# WestLaunch.net
KiCad netlist of a schematic drawn in EAGLE
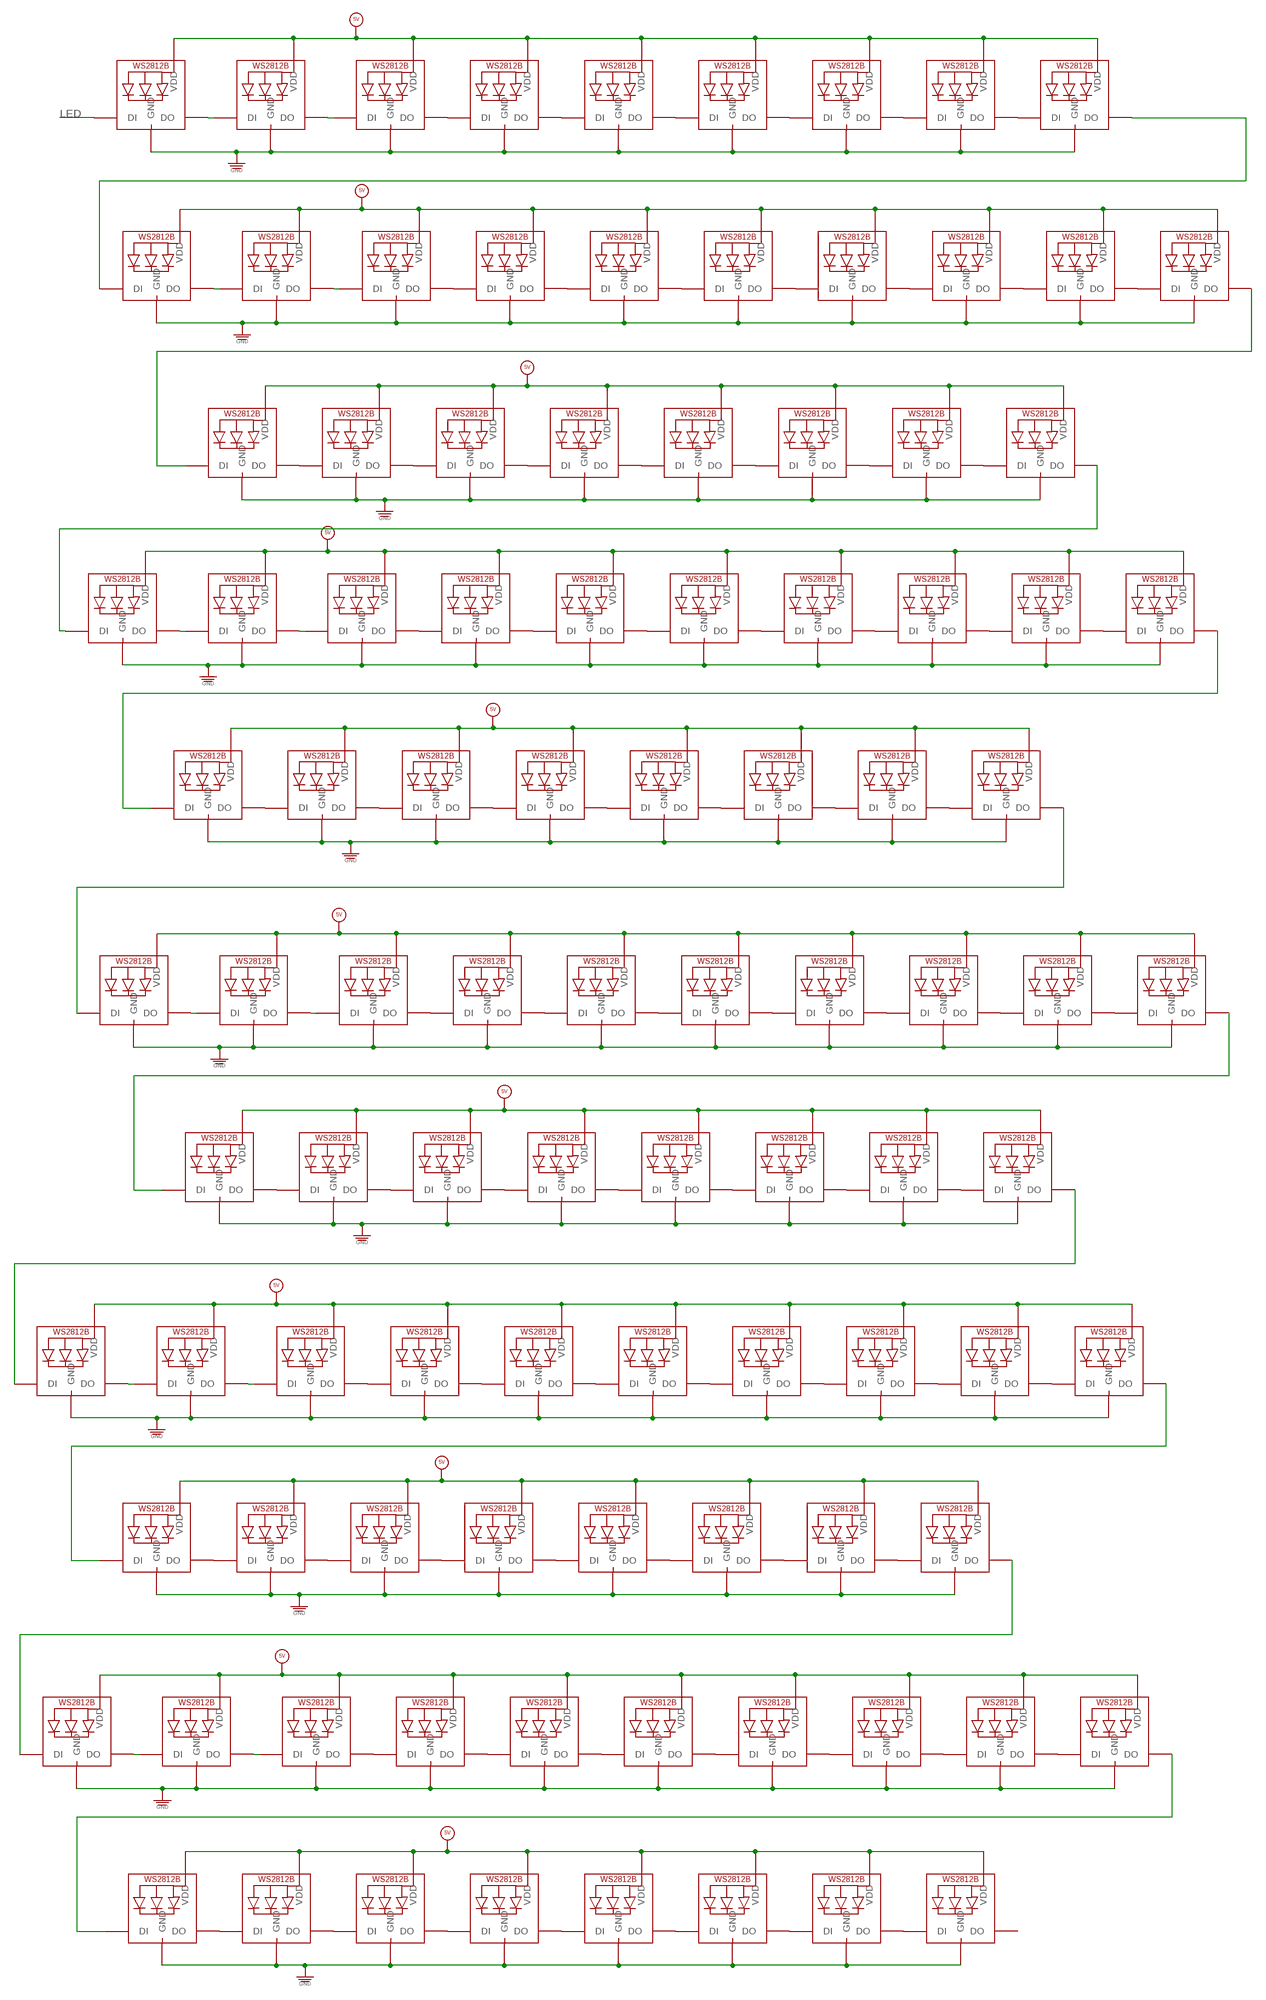
[diagram p0: schematic, sheet 1, part 1 of 2]
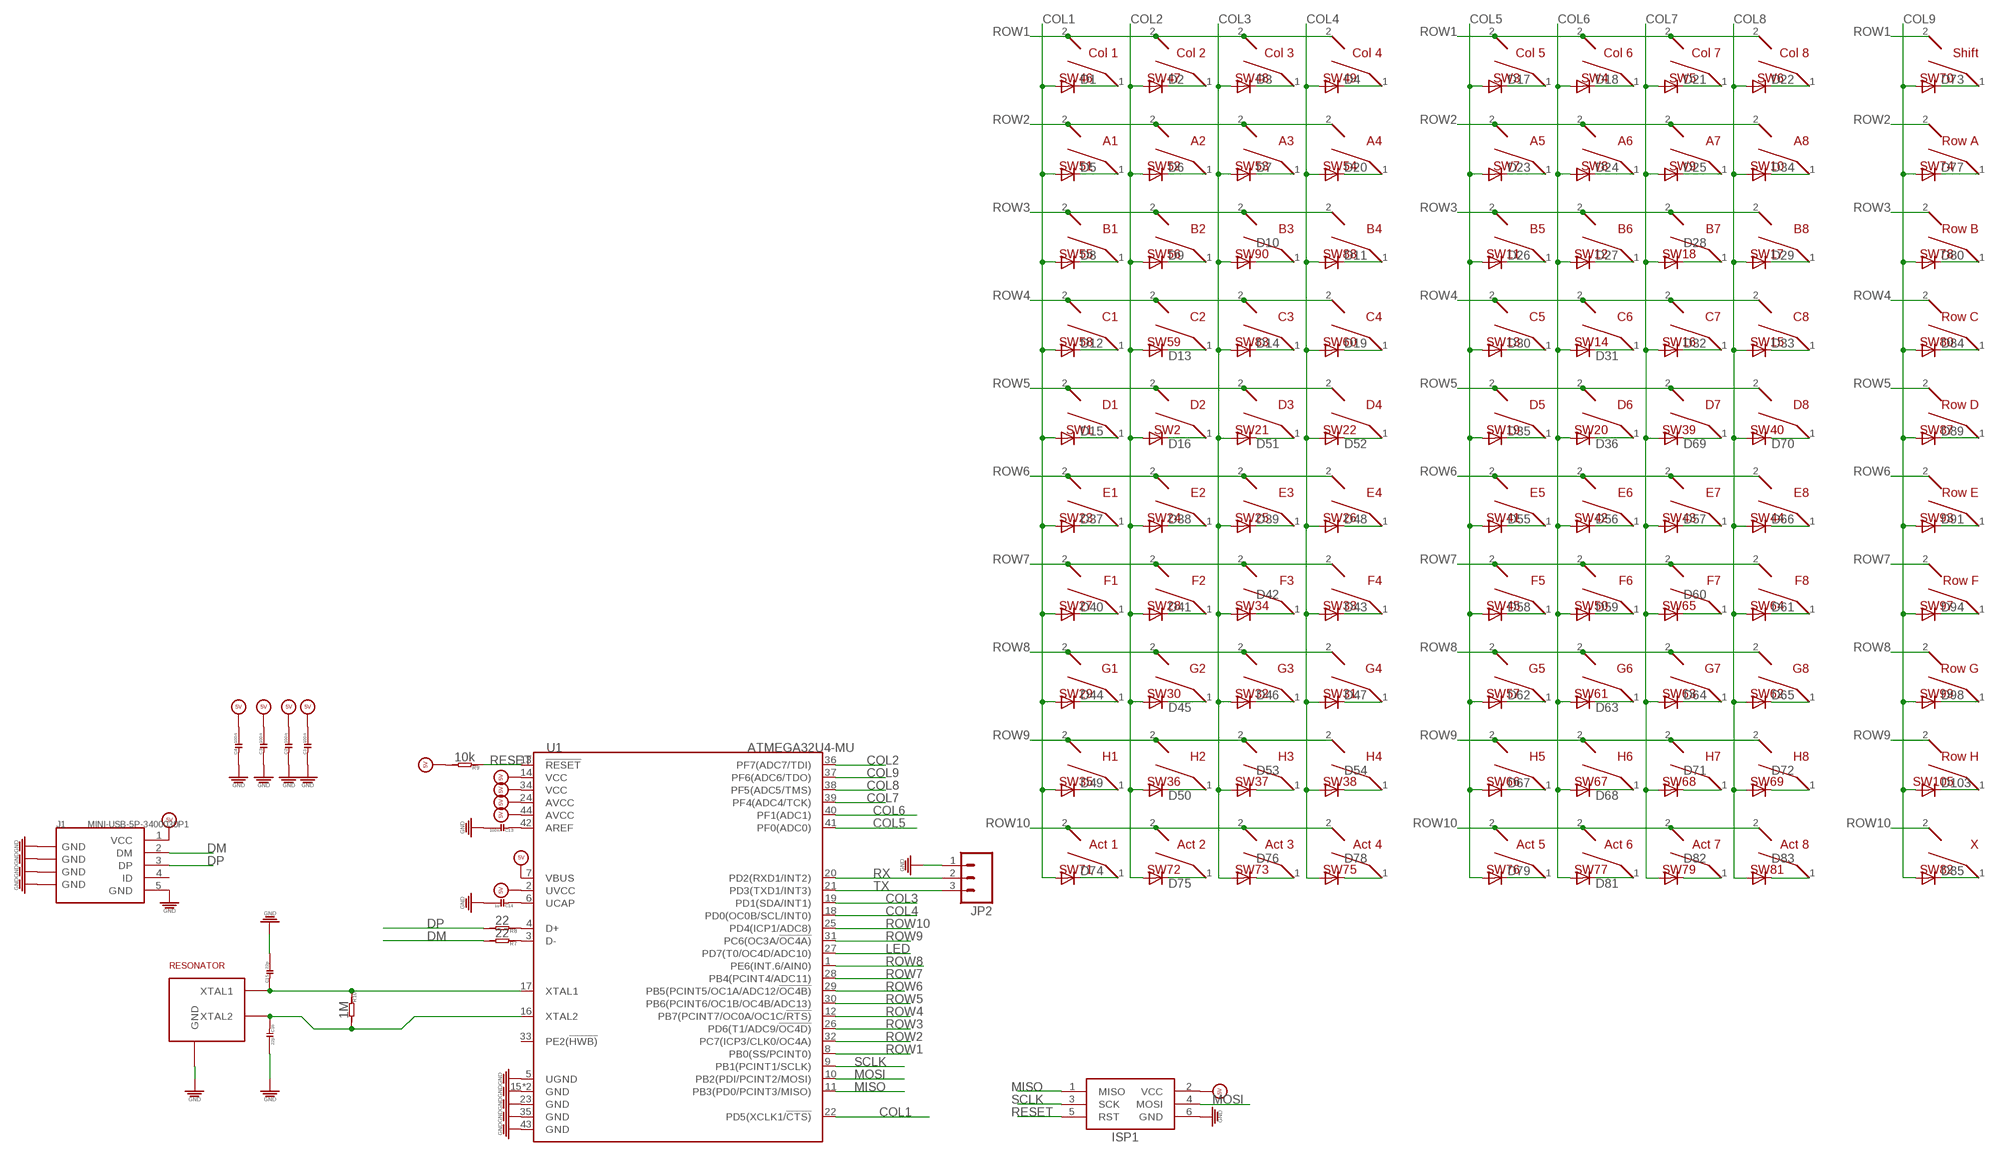
[diagram p1: schematic, sheet 1, part 2 of 2]

(export (version "E")
  (design (tool "Eeschema 10.0.6"))
  (components
    (comp (ref "C1")
      (value "100n")
      (footprint "eagle-import:C0603")
      (libsource (lib "eagle-import") (part "C-0603"))
    )
    (comp (ref "C2")
      (value "100n")
      (footprint "eagle-import:C0603")
      (libsource (lib "eagle-import") (part "C-0603"))
    )
    (comp (ref "C3")
      (value "100n")
      (footprint "eagle-import:C0603")
      (libsource (lib "eagle-import") (part "C-0603"))
    )
    (comp (ref "C4")
      (value "100n")
      (footprint "eagle-import:C0603")
      (libsource (lib "eagle-import") (part "C-0603"))
    )
    (comp (ref "C13")
      (value "100n")
      (footprint "eagle-import:C0603")
      (libsource (lib "eagle-import") (part "C-0603"))
    )
    (comp (ref "C14")
      (value "1u")
      (footprint "eagle-import:C0603")
      (libsource (lib "eagle-import") (part "C-0603"))
    )
    (comp (ref "C15")
      (value "22p")
      (footprint "eagle-import:C0603")
      (libsource (lib "eagle-import") (part "C-0603"))
    )
    (comp (ref "C16")
      (value "22p")
      (footprint "eagle-import:C0603")
      (libsource (lib "eagle-import") (part "C-0603"))
    )
    (comp (ref "D1")
      (value "CGRM4001-G")
      (footprint "eagle-import:SOD-123_MINI-SMA")
      (libsource (lib "eagle-import") (part "CGRM400-G1"))
    )
    (comp (ref "D2")
      (value "CGRM4001-G")
      (footprint "eagle-import:SOD-123_MINI-SMA")
      (libsource (lib "eagle-import") (part "CGRM400-G1"))
    )
    (comp (ref "D3")
      (value "CGRM4001-G")
      (footprint "eagle-import:SOD-123_MINI-SMA")
      (libsource (lib "eagle-import") (part "CGRM400-G1"))
    )
    (comp (ref "D4")
      (value "CGRM4001-G")
      (footprint "eagle-import:SOD-123_MINI-SMA")
      (libsource (lib "eagle-import") (part "CGRM400-G1"))
    )
    (comp (ref "D5")
      (value "CGRM4001-G")
      (footprint "eagle-import:SOD-123_MINI-SMA")
      (libsource (lib "eagle-import") (part "CGRM400-G1"))
    )
    (comp (ref "D6")
      (value "CGRM4001-G")
      (footprint "eagle-import:SOD-123_MINI-SMA")
      (libsource (lib "eagle-import") (part "CGRM400-G1"))
    )
    (comp (ref "D7")
      (value "CGRM4001-G")
      (footprint "eagle-import:SOD-123_MINI-SMA")
      (libsource (lib "eagle-import") (part "CGRM400-G1"))
    )
    (comp (ref "D8")
      (value "CGRM4001-G")
      (footprint "eagle-import:SOD-123_MINI-SMA")
      (libsource (lib "eagle-import") (part "CGRM400-G1"))
    )
    (comp (ref "D9")
      (value "CGRM4001-G")
      (footprint "eagle-import:SOD-123_MINI-SMA")
      (libsource (lib "eagle-import") (part "CGRM400-G1"))
    )
    (comp (ref "D10")
      (value "CGRM4001-G")
      (footprint "eagle-import:SOD-123_MINI-SMA")
      (libsource (lib "eagle-import") (part "CGRM400-G1"))
    )
    (comp (ref "D11")
      (value "CGRM4001-G")
      (footprint "eagle-import:SOD-123_MINI-SMA")
      (libsource (lib "eagle-import") (part "CGRM400-G1"))
    )
    (comp (ref "D12")
      (value "CGRM4001-G")
      (footprint "eagle-import:SOD-123_MINI-SMA")
      (libsource (lib "eagle-import") (part "CGRM400-G1"))
    )
    (comp (ref "D13")
      (value "CGRM4001-G")
      (footprint "eagle-import:SOD-123_MINI-SMA")
      (libsource (lib "eagle-import") (part "CGRM400-G1"))
    )
    (comp (ref "D14")
      (value "CGRM4001-G")
      (footprint "eagle-import:SOD-123_MINI-SMA")
      (libsource (lib "eagle-import") (part "CGRM400-G1"))
    )
    (comp (ref "D15")
      (value "CGRM4001-G")
      (footprint "eagle-import:SOD-123_MINI-SMA")
      (libsource (lib "eagle-import") (part "CGRM400-G1"))
    )
    (comp (ref "D16")
      (value "CGRM4001-G")
      (footprint "eagle-import:SOD-123_MINI-SMA")
      (libsource (lib "eagle-import") (part "CGRM400-G1"))
    )
    (comp (ref "D17")
      (value "CGRM4001-G")
      (footprint "eagle-import:SOD-123_MINI-SMA")
      (libsource (lib "eagle-import") (part "CGRM400-G1"))
    )
    (comp (ref "D18")
      (value "CGRM4001-G")
      (footprint "eagle-import:SOD-123_MINI-SMA")
      (libsource (lib "eagle-import") (part "CGRM400-G1"))
    )
    (comp (ref "D19")
      (value "CGRM4001-G")
      (footprint "eagle-import:SOD-123_MINI-SMA")
      (libsource (lib "eagle-import") (part "CGRM400-G1"))
    )
    (comp (ref "D20")
      (value "CGRM4001-G")
      (footprint "eagle-import:SOD-123_MINI-SMA")
      (libsource (lib "eagle-import") (part "CGRM400-G1"))
    )
    (comp (ref "D21")
      (value "CGRM4001-G")
      (footprint "eagle-import:SOD-123_MINI-SMA")
      (libsource (lib "eagle-import") (part "CGRM400-G1"))
    )
    (comp (ref "D22")
      (value "CGRM4001-G")
      (footprint "eagle-import:SOD-123_MINI-SMA")
      (libsource (lib "eagle-import") (part "CGRM400-G1"))
    )
    (comp (ref "D23")
      (value "CGRM4001-G")
      (footprint "eagle-import:SOD-123_MINI-SMA")
      (libsource (lib "eagle-import") (part "CGRM400-G1"))
    )
    (comp (ref "D24")
      (value "CGRM4001-G")
      (footprint "eagle-import:SOD-123_MINI-SMA")
      (libsource (lib "eagle-import") (part "CGRM400-G1"))
    )
    (comp (ref "D25")
      (value "CGRM4001-G")
      (footprint "eagle-import:SOD-123_MINI-SMA")
      (libsource (lib "eagle-import") (part "CGRM400-G1"))
    )
    (comp (ref "D26")
      (value "CGRM4001-G")
      (footprint "eagle-import:SOD-123_MINI-SMA")
      (libsource (lib "eagle-import") (part "CGRM400-G1"))
    )
    (comp (ref "D27")
      (value "CGRM4001-G")
      (footprint "eagle-import:SOD-123_MINI-SMA")
      (libsource (lib "eagle-import") (part "CGRM400-G1"))
    )
    (comp (ref "D28")
      (value "CGRM4001-G")
      (footprint "eagle-import:SOD-123_MINI-SMA")
      (libsource (lib "eagle-import") (part "CGRM400-G1"))
    )
    (comp (ref "D29")
      (value "CGRM4001-G")
      (footprint "eagle-import:SOD-123_MINI-SMA")
      (libsource (lib "eagle-import") (part "CGRM400-G1"))
    )
    (comp (ref "D30")
      (value "CGRM4001-G")
      (footprint "eagle-import:SOD-123_MINI-SMA")
      (libsource (lib "eagle-import") (part "CGRM400-G1"))
    )
    (comp (ref "D31")
      (value "CGRM4001-G")
      (footprint "eagle-import:SOD-123_MINI-SMA")
      (libsource (lib "eagle-import") (part "CGRM400-G1"))
    )
    (comp (ref "D32")
      (value "CGRM4001-G")
      (footprint "eagle-import:SOD-123_MINI-SMA")
      (libsource (lib "eagle-import") (part "CGRM400-G1"))
    )
    (comp (ref "D33")
      (value "CGRM4001-G")
      (footprint "eagle-import:SOD-123_MINI-SMA")
      (libsource (lib "eagle-import") (part "CGRM400-G1"))
    )
    (comp (ref "D34")
      (value "CGRM4001-G")
      (footprint "eagle-import:SOD-123_MINI-SMA")
      (libsource (lib "eagle-import") (part "CGRM400-G1"))
    )
    (comp (ref "D35")
      (value "CGRM4001-G")
      (footprint "eagle-import:SOD-123_MINI-SMA")
      (libsource (lib "eagle-import") (part "CGRM400-G1"))
    )
    (comp (ref "D36")
      (value "CGRM4001-G")
      (footprint "eagle-import:SOD-123_MINI-SMA")
      (libsource (lib "eagle-import") (part "CGRM400-G1"))
    )
    (comp (ref "D37")
      (value "CGRM4001-G")
      (footprint "eagle-import:SOD-123_MINI-SMA")
      (libsource (lib "eagle-import") (part "CGRM400-G1"))
    )
    (comp (ref "D38")
      (value "CGRM4001-G")
      (footprint "eagle-import:SOD-123_MINI-SMA")
      (libsource (lib "eagle-import") (part "CGRM400-G1"))
    )
    (comp (ref "D39")
      (value "CGRM4001-G")
      (footprint "eagle-import:SOD-123_MINI-SMA")
      (libsource (lib "eagle-import") (part "CGRM400-G1"))
    )
    (comp (ref "D40")
      (value "CGRM4001-G")
      (footprint "eagle-import:SOD-123_MINI-SMA")
      (libsource (lib "eagle-import") (part "CGRM400-G1"))
    )
    (comp (ref "D41")
      (value "CGRM4001-G")
      (footprint "eagle-import:SOD-123_MINI-SMA")
      (libsource (lib "eagle-import") (part "CGRM400-G1"))
    )
    (comp (ref "D42")
      (value "CGRM4001-G")
      (footprint "eagle-import:SOD-123_MINI-SMA")
      (libsource (lib "eagle-import") (part "CGRM400-G1"))
    )
    (comp (ref "D43")
      (value "CGRM4001-G")
      (footprint "eagle-import:SOD-123_MINI-SMA")
      (libsource (lib "eagle-import") (part "CGRM400-G1"))
    )
    (comp (ref "D44")
      (value "CGRM4001-G")
      (footprint "eagle-import:SOD-123_MINI-SMA")
      (libsource (lib "eagle-import") (part "CGRM400-G1"))
    )
    (comp (ref "D45")
      (value "CGRM4001-G")
      (footprint "eagle-import:SOD-123_MINI-SMA")
      (libsource (lib "eagle-import") (part "CGRM400-G1"))
    )
    (comp (ref "D46")
      (value "CGRM4001-G")
      (footprint "eagle-import:SOD-123_MINI-SMA")
      (libsource (lib "eagle-import") (part "CGRM400-G1"))
    )
    (comp (ref "D47")
      (value "CGRM4001-G")
      (footprint "eagle-import:SOD-123_MINI-SMA")
      (libsource (lib "eagle-import") (part "CGRM400-G1"))
    )
    (comp (ref "D48")
      (value "CGRM4001-G")
      (footprint "eagle-import:SOD-123_MINI-SMA")
      (libsource (lib "eagle-import") (part "CGRM400-G1"))
    )
    (comp (ref "D49")
      (value "CGRM4001-G")
      (footprint "eagle-import:SOD-123_MINI-SMA")
      (libsource (lib "eagle-import") (part "CGRM400-G1"))
    )
    (comp (ref "D50")
      (value "CGRM4001-G")
      (footprint "eagle-import:SOD-123_MINI-SMA")
      (libsource (lib "eagle-import") (part "CGRM400-G1"))
    )
    (comp (ref "D51")
      (value "CGRM4001-G")
      (footprint "eagle-import:SOD-123_MINI-SMA")
      (libsource (lib "eagle-import") (part "CGRM400-G1"))
    )
    (comp (ref "D52")
      (value "CGRM4001-G")
      (footprint "eagle-import:SOD-123_MINI-SMA")
      (libsource (lib "eagle-import") (part "CGRM400-G1"))
    )
    (comp (ref "D53")
      (value "CGRM4001-G")
      (footprint "eagle-import:SOD-123_MINI-SMA")
      (libsource (lib "eagle-import") (part "CGRM400-G1"))
    )
    (comp (ref "D54")
      (value "CGRM4001-G")
      (footprint "eagle-import:SOD-123_MINI-SMA")
      (libsource (lib "eagle-import") (part "CGRM400-G1"))
    )
    (comp (ref "D55")
      (value "CGRM4001-G")
      (footprint "eagle-import:SOD-123_MINI-SMA")
      (libsource (lib "eagle-import") (part "CGRM400-G1"))
    )
    (comp (ref "D56")
      (value "CGRM4001-G")
      (footprint "eagle-import:SOD-123_MINI-SMA")
      (libsource (lib "eagle-import") (part "CGRM400-G1"))
    )
    (comp (ref "D57")
      (value "CGRM4001-G")
      (footprint "eagle-import:SOD-123_MINI-SMA")
      (libsource (lib "eagle-import") (part "CGRM400-G1"))
    )
    (comp (ref "D58")
      (value "CGRM4001-G")
      (footprint "eagle-import:SOD-123_MINI-SMA")
      (libsource (lib "eagle-import") (part "CGRM400-G1"))
    )
    (comp (ref "D59")
      (value "CGRM4001-G")
      (footprint "eagle-import:SOD-123_MINI-SMA")
      (libsource (lib "eagle-import") (part "CGRM400-G1"))
    )
    (comp (ref "D60")
      (value "CGRM4001-G")
      (footprint "eagle-import:SOD-123_MINI-SMA")
      (libsource (lib "eagle-import") (part "CGRM400-G1"))
    )
    (comp (ref "D61")
      (value "CGRM4001-G")
      (footprint "eagle-import:SOD-123_MINI-SMA")
      (libsource (lib "eagle-import") (part "CGRM400-G1"))
    )
    (comp (ref "D62")
      (value "CGRM4001-G")
      (footprint "eagle-import:SOD-123_MINI-SMA")
      (libsource (lib "eagle-import") (part "CGRM400-G1"))
    )
    (comp (ref "D63")
      (value "CGRM4001-G")
      (footprint "eagle-import:SOD-123_MINI-SMA")
      (libsource (lib "eagle-import") (part "CGRM400-G1"))
    )
    (comp (ref "D64")
      (value "CGRM4001-G")
      (footprint "eagle-import:SOD-123_MINI-SMA")
      (libsource (lib "eagle-import") (part "CGRM400-G1"))
    )
    (comp (ref "D65")
      (value "CGRM4001-G")
      (footprint "eagle-import:SOD-123_MINI-SMA")
      (libsource (lib "eagle-import") (part "CGRM400-G1"))
    )
    (comp (ref "D66")
      (value "CGRM4001-G")
      (footprint "eagle-import:SOD-123_MINI-SMA")
      (libsource (lib "eagle-import") (part "CGRM400-G1"))
    )
    (comp (ref "D67")
      (value "CGRM4001-G")
      (footprint "eagle-import:SOD-123_MINI-SMA")
      (libsource (lib "eagle-import") (part "CGRM400-G1"))
    )
    (comp (ref "D68")
      (value "CGRM4001-G")
      (footprint "eagle-import:SOD-123_MINI-SMA")
      (libsource (lib "eagle-import") (part "CGRM400-G1"))
    )
    (comp (ref "D69")
      (value "CGRM4001-G")
      (footprint "eagle-import:SOD-123_MINI-SMA")
      (libsource (lib "eagle-import") (part "CGRM400-G1"))
    )
    (comp (ref "D70")
      (value "CGRM4001-G")
      (footprint "eagle-import:SOD-123_MINI-SMA")
      (libsource (lib "eagle-import") (part "CGRM400-G1"))
    )
    (comp (ref "D71")
      (value "CGRM4001-G")
      (footprint "eagle-import:SOD-123_MINI-SMA")
      (libsource (lib "eagle-import") (part "CGRM400-G1"))
    )
    (comp (ref "D72")
      (value "CGRM4001-G")
      (footprint "eagle-import:SOD-123_MINI-SMA")
      (libsource (lib "eagle-import") (part "CGRM400-G1"))
    )
    (comp (ref "D73")
      (value "CGRM4001-G")
      (footprint "eagle-import:SOD-123_MINI-SMA")
      (libsource (lib "eagle-import") (part "CGRM400-G1"))
    )
    (comp (ref "D74")
      (value "CGRM4001-G")
      (footprint "eagle-import:SOD-123_MINI-SMA")
      (libsource (lib "eagle-import") (part "CGRM400-G1"))
    )
    (comp (ref "D75")
      (value "CGRM4001-G")
      (footprint "eagle-import:SOD-123_MINI-SMA")
      (libsource (lib "eagle-import") (part "CGRM400-G1"))
    )
    (comp (ref "D76")
      (value "CGRM4001-G")
      (footprint "eagle-import:SOD-123_MINI-SMA")
      (libsource (lib "eagle-import") (part "CGRM400-G1"))
    )
    (comp (ref "D77")
      (value "CGRM4001-G")
      (footprint "eagle-import:SOD-123_MINI-SMA")
      (libsource (lib "eagle-import") (part "CGRM400-G1"))
    )
    (comp (ref "D78")
      (value "CGRM4001-G")
      (footprint "eagle-import:SOD-123_MINI-SMA")
      (libsource (lib "eagle-import") (part "CGRM400-G1"))
    )
    (comp (ref "D79")
      (value "CGRM4001-G")
      (footprint "eagle-import:SOD-123_MINI-SMA")
      (libsource (lib "eagle-import") (part "CGRM400-G1"))
    )
    (comp (ref "D80")
      (value "CGRM4001-G")
      (footprint "eagle-import:SOD-123_MINI-SMA")
      (libsource (lib "eagle-import") (part "CGRM400-G1"))
    )
    (comp (ref "D81")
      (value "CGRM4001-G")
      (footprint "eagle-import:SOD-123_MINI-SMA")
      (libsource (lib "eagle-import") (part "CGRM400-G1"))
    )
    (comp (ref "D82")
      (value "CGRM4001-G")
      (footprint "eagle-import:SOD-123_MINI-SMA")
      (libsource (lib "eagle-import") (part "CGRM400-G1"))
    )
    (comp (ref "D83")
      (value "CGRM4001-G")
      (footprint "eagle-import:SOD-123_MINI-SMA")
      (libsource (lib "eagle-import") (part "CGRM400-G1"))
    )
    (comp (ref "D84")
      (value "CGRM4001-G")
      (footprint "eagle-import:SOD-123_MINI-SMA")
      (libsource (lib "eagle-import") (part "CGRM400-G1"))
    )
    (comp (ref "D85")
      (value "CGRM4001-G")
      (footprint "eagle-import:SOD-123_MINI-SMA")
      (libsource (lib "eagle-import") (part "CGRM400-G1"))
    )
    (comp (ref "D89")
      (value "CGRM4001-G")
      (footprint "eagle-import:SOD-123_MINI-SMA")
      (libsource (lib "eagle-import") (part "CGRM400-G1"))
    )
    (comp (ref "D91")
      (value "CGRM4001-G")
      (footprint "eagle-import:SOD-123_MINI-SMA")
      (libsource (lib "eagle-import") (part "CGRM400-G1"))
    )
    (comp (ref "D94")
      (value "CGRM4001-G")
      (footprint "eagle-import:SOD-123_MINI-SMA")
      (libsource (lib "eagle-import") (part "CGRM400-G1"))
    )
    (comp (ref "D98")
      (value "CGRM4001-G")
      (footprint "eagle-import:SOD-123_MINI-SMA")
      (libsource (lib "eagle-import") (part "CGRM400-G1"))
    )
    (comp (ref "D103")
      (value "CGRM4001-G")
      (footprint "eagle-import:SOD-123_MINI-SMA")
      (libsource (lib "eagle-import") (part "CGRM400-G1"))
    )
    (comp (ref "ISP1")
      (value "AVRISP-6")
      (footprint "eagle-import:AVRISP")
      (libsource (lib "eagle-import") (part "AVRISP-6"))
    )
    (comp (ref "J1")
      (value "MINI-USB-5P-3400030P1")
      (footprint "eagle-import:MINI-B-5P-SMD")
      (libsource (lib "eagle-import") (part "MINI-USB-5P-3400030P1"))
    )
    (comp (ref "JP2")
      (value "M03PTH")
      (footprint "eagle-import:1X03")
      (fields (field (name "DESC") "Serial"))
      (libsource (lib "eagle-import") (part "M03PTH"))
    )
    (comp (ref "LED1")
      (value "WS2812B3535")
      (footprint "eagle-import:LED3535")
      (libsource (lib "eagle-import") (part "WS2812B3535"))
    )
    (comp (ref "LED2")
      (value "WS2812B3535")
      (footprint "eagle-import:LED3535")
      (libsource (lib "eagle-import") (part "WS2812B3535"))
    )
    (comp (ref "LED3")
      (value "WS2812B3535")
      (footprint "eagle-import:LED3535")
      (libsource (lib "eagle-import") (part "WS2812B3535"))
    )
    (comp (ref "LED4")
      (value "WS2812B3535")
      (footprint "eagle-import:LED3535")
      (libsource (lib "eagle-import") (part "WS2812B3535"))
    )
    (comp (ref "LED5")
      (value "WS2812B3535")
      (footprint "eagle-import:LED3535")
      (libsource (lib "eagle-import") (part "WS2812B3535"))
    )
    (comp (ref "LED6")
      (value "WS2812B3535")
      (footprint "eagle-import:LED3535")
      (libsource (lib "eagle-import") (part "WS2812B3535"))
    )
    (comp (ref "LED7")
      (value "WS2812B3535")
      (footprint "eagle-import:LED3535")
      (libsource (lib "eagle-import") (part "WS2812B3535"))
    )
    (comp (ref "LED8")
      (value "WS2812B3535")
      (footprint "eagle-import:LED3535")
      (libsource (lib "eagle-import") (part "WS2812B3535"))
    )
    (comp (ref "LED9")
      (value "WS2812B3535")
      (footprint "eagle-import:LED3535")
      (libsource (lib "eagle-import") (part "WS2812B3535"))
    )
    (comp (ref "LED10")
      (value "WS2812B3535")
      (footprint "eagle-import:LED3535")
      (libsource (lib "eagle-import") (part "WS2812B3535"))
    )
    (comp (ref "LED11")
      (value "WS2812B3535")
      (footprint "eagle-import:LED3535")
      (libsource (lib "eagle-import") (part "WS2812B3535"))
    )
    (comp (ref "LED12")
      (value "WS2812B3535")
      (footprint "eagle-import:LED3535")
      (libsource (lib "eagle-import") (part "WS2812B3535"))
    )
    (comp (ref "LED13")
      (value "WS2812B3535")
      (footprint "eagle-import:LED3535")
      (libsource (lib "eagle-import") (part "WS2812B3535"))
    )
    (comp (ref "LED14")
      (value "WS2812B3535")
      (footprint "eagle-import:LED3535")
      (libsource (lib "eagle-import") (part "WS2812B3535"))
    )
    (comp (ref "LED15")
      (value "WS2812B3535")
      (footprint "eagle-import:LED3535")
      (libsource (lib "eagle-import") (part "WS2812B3535"))
    )
    (comp (ref "LED16")
      (value "WS2812B3535")
      (footprint "eagle-import:LED3535")
      (libsource (lib "eagle-import") (part "WS2812B3535"))
    )
    (comp (ref "LED17")
      (value "WS2812B3535")
      (footprint "eagle-import:LED3535")
      (libsource (lib "eagle-import") (part "WS2812B3535"))
    )
    (comp (ref "LED18")
      (value "WS2812B3535")
      (footprint "eagle-import:LED3535")
      (libsource (lib "eagle-import") (part "WS2812B3535"))
    )
    (comp (ref "LED19")
      (value "WS2812B3535")
      (footprint "eagle-import:LED3535")
      (libsource (lib "eagle-import") (part "WS2812B3535"))
    )
    (comp (ref "LED20")
      (value "WS2812B3535")
      (footprint "eagle-import:LED3535")
      (libsource (lib "eagle-import") (part "WS2812B3535"))
    )
    (comp (ref "LED21")
      (value "WS2812B3535")
      (footprint "eagle-import:LED3535")
      (libsource (lib "eagle-import") (part "WS2812B3535"))
    )
    (comp (ref "LED22")
      (value "WS2812B3535")
      (footprint "eagle-import:LED3535")
      (libsource (lib "eagle-import") (part "WS2812B3535"))
    )
    (comp (ref "LED23")
      (value "WS2812B3535")
      (footprint "eagle-import:LED3535")
      (libsource (lib "eagle-import") (part "WS2812B3535"))
    )
    (comp (ref "LED24")
      (value "WS2812B3535")
      (footprint "eagle-import:LED3535")
      (libsource (lib "eagle-import") (part "WS2812B3535"))
    )
    (comp (ref "LED25")
      (value "WS2812B3535")
      (footprint "eagle-import:LED3535")
      (libsource (lib "eagle-import") (part "WS2812B3535"))
    )
    (comp (ref "LED26")
      (value "WS2812B3535")
      (footprint "eagle-import:LED3535")
      (libsource (lib "eagle-import") (part "WS2812B3535"))
    )
    (comp (ref "LED27")
      (value "WS2812B3535")
      (footprint "eagle-import:LED3535")
      (libsource (lib "eagle-import") (part "WS2812B3535"))
    )
    (comp (ref "LED28")
      (value "WS2812B3535")
      (footprint "eagle-import:LED3535")
      (libsource (lib "eagle-import") (part "WS2812B3535"))
    )
    (comp (ref "LED29")
      (value "WS2812B3535")
      (footprint "eagle-import:LED3535")
      (libsource (lib "eagle-import") (part "WS2812B3535"))
    )
    (comp (ref "LED30")
      (value "WS2812B3535")
      (footprint "eagle-import:LED3535")
      (libsource (lib "eagle-import") (part "WS2812B3535"))
    )
    (comp (ref "LED31")
      (value "WS2812B3535")
      (footprint "eagle-import:LED3535")
      (libsource (lib "eagle-import") (part "WS2812B3535"))
    )
    (comp (ref "LED32")
      (value "WS2812B3535")
      (footprint "eagle-import:LED3535")
      (libsource (lib "eagle-import") (part "WS2812B3535"))
    )
    (comp (ref "LED33")
      (value "WS2812B3535")
      (footprint "eagle-import:LED3535")
      (libsource (lib "eagle-import") (part "WS2812B3535"))
    )
    (comp (ref "LED34")
      (value "WS2812B3535")
      (footprint "eagle-import:LED3535")
      (libsource (lib "eagle-import") (part "WS2812B3535"))
    )
    (comp (ref "LED35")
      (value "WS2812B3535")
      (footprint "eagle-import:LED3535")
      (libsource (lib "eagle-import") (part "WS2812B3535"))
    )
    (comp (ref "LED36")
      (value "WS2812B3535")
      (footprint "eagle-import:LED3535")
      (libsource (lib "eagle-import") (part "WS2812B3535"))
    )
    (comp (ref "LED37")
      (value "WS2812B3535")
      (footprint "eagle-import:LED3535")
      (libsource (lib "eagle-import") (part "WS2812B3535"))
    )
    (comp (ref "LED38")
      (value "WS2812B3535")
      (footprint "eagle-import:LED3535")
      (libsource (lib "eagle-import") (part "WS2812B3535"))
    )
    (comp (ref "LED39")
      (value "WS2812B3535")
      (footprint "eagle-import:LED3535")
      (libsource (lib "eagle-import") (part "WS2812B3535"))
    )
    (comp (ref "LED40")
      (value "WS2812B3535")
      (footprint "eagle-import:LED3535")
      (libsource (lib "eagle-import") (part "WS2812B3535"))
    )
    (comp (ref "LED41")
      (value "WS2812B3535")
      (footprint "eagle-import:LED3535")
      (libsource (lib "eagle-import") (part "WS2812B3535"))
    )
    (comp (ref "LED42")
      (value "WS2812B3535")
      (footprint "eagle-import:LED3535")
      (libsource (lib "eagle-import") (part "WS2812B3535"))
    )
    (comp (ref "LED43")
      (value "WS2812B3535")
      (footprint "eagle-import:LED3535")
      (libsource (lib "eagle-import") (part "WS2812B3535"))
    )
    (comp (ref "LED44")
      (value "WS2812B3535")
      (footprint "eagle-import:LED3535")
      (libsource (lib "eagle-import") (part "WS2812B3535"))
    )
    (comp (ref "LED45")
      (value "WS2812B3535")
      (footprint "eagle-import:LED3535")
      (libsource (lib "eagle-import") (part "WS2812B3535"))
    )
    (comp (ref "LED46")
      (value "WS2812B3535")
      (footprint "eagle-import:LED3535")
      (libsource (lib "eagle-import") (part "WS2812B3535"))
    )
    (comp (ref "LED47")
      (value "WS2812B3535")
      (footprint "eagle-import:LED3535")
      (libsource (lib "eagle-import") (part "WS2812B3535"))
    )
    (comp (ref "LED48")
      (value "WS2812B3535")
      (footprint "eagle-import:LED3535")
      (libsource (lib "eagle-import") (part "WS2812B3535"))
    )
    (comp (ref "LED49")
      (value "WS2812B3535")
      (footprint "eagle-import:LED3535")
      (libsource (lib "eagle-import") (part "WS2812B3535"))
    )
    (comp (ref "LED50")
      (value "WS2812B3535")
      (footprint "eagle-import:LED3535")
      (libsource (lib "eagle-import") (part "WS2812B3535"))
    )
    (comp (ref "LED51")
      (value "WS2812B3535")
      (footprint "eagle-import:LED3535")
      (libsource (lib "eagle-import") (part "WS2812B3535"))
    )
    (comp (ref "LED52")
      (value "WS2812B3535")
      (footprint "eagle-import:LED3535")
      (libsource (lib "eagle-import") (part "WS2812B3535"))
    )
    (comp (ref "LED53")
      (value "WS2812B3535")
      (footprint "eagle-import:LED3535")
      (libsource (lib "eagle-import") (part "WS2812B3535"))
    )
    (comp (ref "LED54")
      (value "WS2812B3535")
      (footprint "eagle-import:LED3535")
      (libsource (lib "eagle-import") (part "WS2812B3535"))
    )
    (comp (ref "LED55")
      (value "WS2812B3535")
      (footprint "eagle-import:LED3535")
      (libsource (lib "eagle-import") (part "WS2812B3535"))
    )
    (comp (ref "LED56")
      (value "WS2812B3535")
      (footprint "eagle-import:LED3535")
      (libsource (lib "eagle-import") (part "WS2812B3535"))
    )
    (comp (ref "LED57")
      (value "WS2812B3535")
      (footprint "eagle-import:LED3535")
      (libsource (lib "eagle-import") (part "WS2812B3535"))
    )
    (comp (ref "LED58")
      (value "WS2812B3535")
      (footprint "eagle-import:LED3535")
      (libsource (lib "eagle-import") (part "WS2812B3535"))
    )
    (comp (ref "LED59")
      (value "WS2812B3535")
      (footprint "eagle-import:LED3535")
      (libsource (lib "eagle-import") (part "WS2812B3535"))
    )
    (comp (ref "LED60")
      (value "WS2812B3535")
      (footprint "eagle-import:LED3535")
      (libsource (lib "eagle-import") (part "WS2812B3535"))
    )
    (comp (ref "LED61")
      (value "WS2812B3535")
      (footprint "eagle-import:LED3535")
      (libsource (lib "eagle-import") (part "WS2812B3535"))
    )
    (comp (ref "LED62")
      (value "WS2812B3535")
      (footprint "eagle-import:LED3535")
      (libsource (lib "eagle-import") (part "WS2812B3535"))
    )
    (comp (ref "LED63")
      (value "WS2812B3535")
      (footprint "eagle-import:LED3535")
      (libsource (lib "eagle-import") (part "WS2812B3535"))
    )
    (comp (ref "LED64")
      (value "WS2812B3535")
      (footprint "eagle-import:LED3535")
      (libsource (lib "eagle-import") (part "WS2812B3535"))
    )
    (comp (ref "LED65")
      (value "WS2812B3535")
      (footprint "eagle-import:LED3535")
      (libsource (lib "eagle-import") (part "WS2812B3535"))
    )
    (comp (ref "LED66")
      (value "WS2812B3535")
      (footprint "eagle-import:LED3535")
      (libsource (lib "eagle-import") (part "WS2812B3535"))
    )
    (comp (ref "LED67")
      (value "WS2812B3535")
      (footprint "eagle-import:LED3535")
      (libsource (lib "eagle-import") (part "WS2812B3535"))
    )
    (comp (ref "LED68")
      (value "WS2812B3535")
      (footprint "eagle-import:LED3535")
      (libsource (lib "eagle-import") (part "WS2812B3535"))
    )
    (comp (ref "LED69")
      (value "WS2812B3535")
      (footprint "eagle-import:LED3535")
      (libsource (lib "eagle-import") (part "WS2812B3535"))
    )
    (comp (ref "LED70")
      (value "WS2812B3535")
      (footprint "eagle-import:LED3535")
      (libsource (lib "eagle-import") (part "WS2812B3535"))
    )
    (comp (ref "LED71")
      (value "WS2812B3535")
      (footprint "eagle-import:LED3535")
      (libsource (lib "eagle-import") (part "WS2812B3535"))
    )
    (comp (ref "LED72")
      (value "WS2812B3535")
      (footprint "eagle-import:LED3535")
      (libsource (lib "eagle-import") (part "WS2812B3535"))
    )
    (comp (ref "LED73")
      (value "WS2812B3535")
      (footprint "eagle-import:LED3535")
      (libsource (lib "eagle-import") (part "WS2812B3535"))
    )
    (comp (ref "LED74")
      (value "WS2812B3535")
      (footprint "eagle-import:LED3535")
      (libsource (lib "eagle-import") (part "WS2812B3535"))
    )
    (comp (ref "LED75")
      (value "WS2812B3535")
      (footprint "eagle-import:LED3535")
      (libsource (lib "eagle-import") (part "WS2812B3535"))
    )
    (comp (ref "LED76")
      (value "WS2812B3535")
      (footprint "eagle-import:LED3535")
      (libsource (lib "eagle-import") (part "WS2812B3535"))
    )
    (comp (ref "LED77")
      (value "WS2812B3535")
      (footprint "eagle-import:LED3535")
      (libsource (lib "eagle-import") (part "WS2812B3535"))
    )
    (comp (ref "LED78")
      (value "WS2812B3535")
      (footprint "eagle-import:LED3535")
      (libsource (lib "eagle-import") (part "WS2812B3535"))
    )
    (comp (ref "LED79")
      (value "WS2812B3535")
      (footprint "eagle-import:LED3535")
      (libsource (lib "eagle-import") (part "WS2812B3535"))
    )
    (comp (ref "LED80")
      (value "WS2812B3535")
      (footprint "eagle-import:LED3535")
      (libsource (lib "eagle-import") (part "WS2812B3535"))
    )
    (comp (ref "LED81")
      (value "WS2812B3535")
      (footprint "eagle-import:LED3535")
      (libsource (lib "eagle-import") (part "WS2812B3535"))
    )
    (comp (ref "LED82")
      (value "WS2812B3535")
      (footprint "eagle-import:LED3535")
      (libsource (lib "eagle-import") (part "WS2812B3535"))
    )
    (comp (ref "LED83")
      (value "WS2812B3535")
      (footprint "eagle-import:LED3535")
      (libsource (lib "eagle-import") (part "WS2812B3535"))
    )
    (comp (ref "LED84")
      (value "WS2812B3535")
      (footprint "eagle-import:LED3535")
      (libsource (lib "eagle-import") (part "WS2812B3535"))
    )
    (comp (ref "LED85")
      (value "WS2812B3535")
      (footprint "eagle-import:LED3535")
      (libsource (lib "eagle-import") (part "WS2812B3535"))
    )
    (comp (ref "LED86")
      (value "WS2812B3535")
      (footprint "eagle-import:LED3535")
      (libsource (lib "eagle-import") (part "WS2812B3535"))
    )
    (comp (ref "LED87")
      (value "WS2812B3535")
      (footprint "eagle-import:LED3535")
      (libsource (lib "eagle-import") (part "WS2812B3535"))
    )
    (comp (ref "LED88")
      (value "WS2812B3535")
      (footprint "eagle-import:LED3535")
      (libsource (lib "eagle-import") (part "WS2812B3535"))
    )
    (comp (ref "LED89")
      (value "WS2812B3535")
      (footprint "eagle-import:LED3535")
      (libsource (lib "eagle-import") (part "WS2812B3535"))
    )
    (comp (ref "LED90")
      (value "WS2812B3535")
      (footprint "eagle-import:LED3535")
      (libsource (lib "eagle-import") (part "WS2812B3535"))
    )
    (comp (ref "LED91")
      (value "WS2812B3535")
      (footprint "eagle-import:LED3535")
      (libsource (lib "eagle-import") (part "WS2812B3535"))
    )
    (comp (ref "LED92")
      (value "WS2812B3535")
      (footprint "eagle-import:LED3535")
      (libsource (lib "eagle-import") (part "WS2812B3535"))
    )
    (comp (ref "LED93")
      (value "WS2812B3535")
      (footprint "eagle-import:LED3535")
      (libsource (lib "eagle-import") (part "WS2812B3535"))
    )
    (comp (ref "LED94")
      (value "WS2812B3535")
      (footprint "eagle-import:LED3535")
      (libsource (lib "eagle-import") (part "WS2812B3535"))
    )
    (comp (ref "LED95")
      (value "WS2812B3535")
      (footprint "eagle-import:LED3535")
      (libsource (lib "eagle-import") (part "WS2812B3535"))
    )
    (comp (ref "LED96")
      (value "WS2812B3535")
      (footprint "eagle-import:LED3535")
      (libsource (lib "eagle-import") (part "WS2812B3535"))
    )
    (comp (ref "LED97")
      (value "WS2812B3535")
      (footprint "eagle-import:LED3535")
      (libsource (lib "eagle-import") (part "WS2812B3535"))
    )
    (comp (ref "LED98")
      (value "WS2812B3535")
      (footprint "eagle-import:LED3535")
      (libsource (lib "eagle-import") (part "WS2812B3535"))
    )
    (comp (ref "LED99")
      (value "WS2812B3535")
      (footprint "eagle-import:LED3535")
      (libsource (lib "eagle-import") (part "WS2812B3535"))
    )
    (comp (ref "R7")
      (value "22")
      (footprint "eagle-import:R0603")
      (libsource (lib "eagle-import") (part "R-0603"))
    )
    (comp (ref "R8")
      (value "22")
      (footprint "eagle-import:R0603")
      (libsource (lib "eagle-import") (part "R-0603"))
    )
    (comp (ref "R9")
      (value "10k")
      (footprint "eagle-import:R0603")
      (libsource (lib "eagle-import") (part "R-0603"))
    )
    (comp (ref "R10")
      (value "1M")
      (footprint "eagle-import:R0603")
      (libsource (lib "eagle-import") (part "R-0603"))
    )
    (comp (ref "SW1")
      (value "D1")
      (footprint "eagle-import:MX1A-XXNW")
      (libsource (lib "eagle-import") (part "CHERRY_MX_WITH_FIXING_PINS"))
    )
    (comp (ref "SW2")
      (value "D2")
      (footprint "eagle-import:MX1A-XXNW")
      (libsource (lib "eagle-import") (part "CHERRY_MX_WITH_FIXING_PINS"))
    )
    (comp (ref "SW3")
      (value "Col 5")
      (footprint "eagle-import:MX1A-XXNW")
      (libsource (lib "eagle-import") (part "CHERRY_MX_WITH_FIXING_PINS"))
    )
    (comp (ref "SW4")
      (value "Col 6")
      (footprint "eagle-import:MX1A-XXNW")
      (libsource (lib "eagle-import") (part "CHERRY_MX_WITH_FIXING_PINS"))
    )
    (comp (ref "SW5")
      (value "Col 7")
      (footprint "eagle-import:MX1A-XXNW")
      (libsource (lib "eagle-import") (part "CHERRY_MX_WITH_FIXING_PINS"))
    )
    (comp (ref "SW6")
      (value "Col 8")
      (footprint "eagle-import:MX1A-XXNW")
      (libsource (lib "eagle-import") (part "CHERRY_MX_WITH_FIXING_PINS"))
    )
    (comp (ref "SW7")
      (value "A5")
      (footprint "eagle-import:MX1A-XXNW")
      (libsource (lib "eagle-import") (part "CHERRY_MX_WITH_FIXING_PINS"))
    )
    (comp (ref "SW8")
      (value "A6")
      (footprint "eagle-import:MX1A-XXNW")
      (libsource (lib "eagle-import") (part "CHERRY_MX_WITH_FIXING_PINS"))
    )
    (comp (ref "SW9")
      (value "A7")
      (footprint "eagle-import:MX1A-XXNW")
      (libsource (lib "eagle-import") (part "CHERRY_MX_WITH_FIXING_PINS"))
    )
    (comp (ref "SW10")
      (value "A8")
      (footprint "eagle-import:MX1A-XXNW")
      (libsource (lib "eagle-import") (part "CHERRY_MX_WITH_FIXING_PINS"))
    )
    (comp (ref "SW11")
      (value "B5")
      (footprint "eagle-import:MX1A-XXNW")
      (libsource (lib "eagle-import") (part "CHERRY_MX_WITH_FIXING_PINS"))
    )
    (comp (ref "SW12")
      (value "B6")
      (footprint "eagle-import:MX1A-XXNW")
      (libsource (lib "eagle-import") (part "CHERRY_MX_WITH_FIXING_PINS"))
    )
    (comp (ref "SW13")
      (value "C5")
      (footprint "eagle-import:MX1A-XXNW")
      (libsource (lib "eagle-import") (part "CHERRY_MX_WITH_FIXING_PINS"))
    )
    (comp (ref "SW14")
      (value "C6")
      (footprint "eagle-import:MX1A-XXNW")
      (libsource (lib "eagle-import") (part "CHERRY_MX_WITH_FIXING_PINS"))
    )
    (comp (ref "SW15")
      (value "C8")
      (footprint "eagle-import:MX1A-XXNW")
      (libsource (lib "eagle-import") (part "CHERRY_MX_WITH_FIXING_PINS"))
    )
    (comp (ref "SW16")
      (value "C7")
      (footprint "eagle-import:MX1A-XXNW")
      (libsource (lib "eagle-import") (part "CHERRY_MX_WITH_FIXING_PINS"))
    )
    (comp (ref "SW17")
      (value "B8")
      (footprint "eagle-import:MX1A-XXNW")
      (libsource (lib "eagle-import") (part "CHERRY_MX_WITH_FIXING_PINS"))
    )
    (comp (ref "SW18")
      (value "B7")
      (footprint "eagle-import:MX1A-XXNW")
      (libsource (lib "eagle-import") (part "CHERRY_MX_WITH_FIXING_PINS"))
    )
    (comp (ref "SW19")
      (value "D5")
      (footprint "eagle-import:MX1A-XXNW")
      (libsource (lib "eagle-import") (part "CHERRY_MX_WITH_FIXING_PINS"))
    )
    (comp (ref "SW20")
      (value "D6")
      (footprint "eagle-import:MX1A-XXNW")
      (libsource (lib "eagle-import") (part "CHERRY_MX_WITH_FIXING_PINS"))
    )
    (comp (ref "SW21")
      (value "D3")
      (footprint "eagle-import:MX1A-XXNW")
      (libsource (lib "eagle-import") (part "CHERRY_MX_WITH_FIXING_PINS"))
    )
    (comp (ref "SW22")
      (value "D4")
      (footprint "eagle-import:MX1A-XXNW")
      (libsource (lib "eagle-import") (part "CHERRY_MX_WITH_FIXING_PINS"))
    )
    (comp (ref "SW23")
      (value "E1")
      (footprint "eagle-import:MX1A-XXNW")
      (libsource (lib "eagle-import") (part "CHERRY_MX_WITH_FIXING_PINS"))
    )
    (comp (ref "SW24")
      (value "E2")
      (footprint "eagle-import:MX1A-XXNW")
      (libsource (lib "eagle-import") (part "CHERRY_MX_WITH_FIXING_PINS"))
    )
    (comp (ref "SW25")
      (value "E3")
      (footprint "eagle-import:MX1A-XXNW")
      (libsource (lib "eagle-import") (part "CHERRY_MX_WITH_FIXING_PINS"))
    )
    (comp (ref "SW26")
      (value "E4")
      (footprint "eagle-import:MX1A-XXNW")
      (libsource (lib "eagle-import") (part "CHERRY_MX_WITH_FIXING_PINS"))
    )
    (comp (ref "SW27")
      (value "F1")
      (footprint "eagle-import:MX1A-XXNW")
      (libsource (lib "eagle-import") (part "CHERRY_MX_WITH_FIXING_PINS"))
    )
    (comp (ref "SW28")
      (value "F2")
      (footprint "eagle-import:MX1A-XXNW")
      (libsource (lib "eagle-import") (part "CHERRY_MX_WITH_FIXING_PINS"))
    )
    (comp (ref "SW29")
      (value "G1")
      (footprint "eagle-import:MX1A-XXNW")
      (libsource (lib "eagle-import") (part "CHERRY_MX_WITH_FIXING_PINS"))
    )
    (comp (ref "SW30")
      (value "G2")
      (footprint "eagle-import:MX1A-XXNW")
      (libsource (lib "eagle-import") (part "CHERRY_MX_WITH_FIXING_PINS"))
    )
    (comp (ref "SW31")
      (value "G4")
      (footprint "eagle-import:MX1A-XXNW")
      (libsource (lib "eagle-import") (part "CHERRY_MX_WITH_FIXING_PINS"))
    )
    (comp (ref "SW32")
      (value "G3")
      (footprint "eagle-import:MX1A-XXNW")
      (libsource (lib "eagle-import") (part "CHERRY_MX_WITH_FIXING_PINS"))
    )
    (comp (ref "SW33")
      (value "F4")
      (footprint "eagle-import:MX1A-XXNW")
      (libsource (lib "eagle-import") (part "CHERRY_MX_WITH_FIXING_PINS"))
    )
    (comp (ref "SW34")
      (value "F3")
      (footprint "eagle-import:MX1A-XXNW")
      (libsource (lib "eagle-import") (part "CHERRY_MX_WITH_FIXING_PINS"))
    )
    (comp (ref "SW35")
      (value "H1")
      (footprint "eagle-import:MX1A-XXNW")
      (libsource (lib "eagle-import") (part "CHERRY_MX_WITH_FIXING_PINS"))
    )
    (comp (ref "SW36")
      (value "H2")
      (footprint "eagle-import:MX1A-XXNW")
      (libsource (lib "eagle-import") (part "CHERRY_MX_WITH_FIXING_PINS"))
    )
    (comp (ref "SW37")
      (value "H3")
      (footprint "eagle-import:MX1A-XXNW")
      (libsource (lib "eagle-import") (part "CHERRY_MX_WITH_FIXING_PINS"))
    )
    (comp (ref "SW38")
      (value "H4")
      (footprint "eagle-import:MX1A-XXNW")
      (libsource (lib "eagle-import") (part "CHERRY_MX_WITH_FIXING_PINS"))
    )
    (comp (ref "SW39")
      (value "D7")
      (footprint "eagle-import:MX1A-XXNW")
      (libsource (lib "eagle-import") (part "CHERRY_MX_WITH_FIXING_PINS"))
    )
    (comp (ref "SW40")
      (value "D8")
      (footprint "eagle-import:MX1A-XXNW")
      (libsource (lib "eagle-import") (part "CHERRY_MX_WITH_FIXING_PINS"))
    )
    (comp (ref "SW41")
      (value "E5")
      (footprint "eagle-import:MX1A-XXNW")
      (libsource (lib "eagle-import") (part "CHERRY_MX_WITH_FIXING_PINS"))
    )
    (comp (ref "SW42")
      (value "E6")
      (footprint "eagle-import:MX1A-XXNW")
      (libsource (lib "eagle-import") (part "CHERRY_MX_WITH_FIXING_PINS"))
    )
    (comp (ref "SW43")
      (value "E7")
      (footprint "eagle-import:MX1A-XXNW")
      (libsource (lib "eagle-import") (part "CHERRY_MX_WITH_FIXING_PINS"))
    )
    (comp (ref "SW44")
      (value "E8")
      (footprint "eagle-import:MX1A-XXNW")
      (libsource (lib "eagle-import") (part "CHERRY_MX_WITH_FIXING_PINS"))
    )
    (comp (ref "SW45")
      (value "F5")
      (footprint "eagle-import:MX1A-XXNW")
      (libsource (lib "eagle-import") (part "CHERRY_MX_WITH_FIXING_PINS"))
    )
    (comp (ref "SW46")
      (value "Col 1")
      (footprint "eagle-import:MX1A-XXNW")
      (libsource (lib "eagle-import") (part "CHERRY_MX_WITH_FIXING_PINS"))
    )
    (comp (ref "SW47")
      (value "Col 2")
      (footprint "eagle-import:MX1A-XXNW")
      (libsource (lib "eagle-import") (part "CHERRY_MX_WITH_FIXING_PINS"))
    )
    (comp (ref "SW48")
      (value "Col 3")
      (footprint "eagle-import:MX1A-XXNW")
      (libsource (lib "eagle-import") (part "CHERRY_MX_WITH_FIXING_PINS"))
    )
    (comp (ref "SW49")
      (value "Col 4")
      (footprint "eagle-import:MX1A-XXNW")
      (libsource (lib "eagle-import") (part "CHERRY_MX_WITH_FIXING_PINS"))
    )
    (comp (ref "SW50")
      (value "F6")
      (footprint "eagle-import:MX1A-XXNW")
      (libsource (lib "eagle-import") (part "CHERRY_MX_WITH_FIXING_PINS"))
    )
    (comp (ref "SW51")
      (value "A1")
      (footprint "eagle-import:MX1A-XXNW")
      (libsource (lib "eagle-import") (part "CHERRY_MX_WITH_FIXING_PINS"))
    )
    (comp (ref "SW52")
      (value "A2")
      (footprint "eagle-import:MX1A-XXNW")
      (libsource (lib "eagle-import") (part "CHERRY_MX_WITH_FIXING_PINS"))
    )
    (comp (ref "SW53")
      (value "A3")
      (footprint "eagle-import:MX1A-XXNW")
      (libsource (lib "eagle-import") (part "CHERRY_MX_WITH_FIXING_PINS"))
    )
    (comp (ref "SW54")
      (value "A4")
      (footprint "eagle-import:MX1A-XXNW")
      (libsource (lib "eagle-import") (part "CHERRY_MX_WITH_FIXING_PINS"))
    )
    (comp (ref "SW55")
      (value "B1")
      (footprint "eagle-import:MX1A-XXNW")
      (libsource (lib "eagle-import") (part "CHERRY_MX_WITH_FIXING_PINS"))
    )
    (comp (ref "SW56")
      (value "B2")
      (footprint "eagle-import:MX1A-XXNW")
      (libsource (lib "eagle-import") (part "CHERRY_MX_WITH_FIXING_PINS"))
    )
    (comp (ref "SW57")
      (value "G5")
      (footprint "eagle-import:MX1A-XXNW")
      (libsource (lib "eagle-import") (part "CHERRY_MX_WITH_FIXING_PINS"))
    )
    (comp (ref "SW58")
      (value "C1")
      (footprint "eagle-import:MX1A-XXNW")
      (libsource (lib "eagle-import") (part "CHERRY_MX_WITH_FIXING_PINS"))
    )
    (comp (ref "SW59")
      (value "C2")
      (footprint "eagle-import:MX1A-XXNW")
      (libsource (lib "eagle-import") (part "CHERRY_MX_WITH_FIXING_PINS"))
    )
    (comp (ref "SW60")
      (value "C4")
      (footprint "eagle-import:MX1A-XXNW")
      (libsource (lib "eagle-import") (part "CHERRY_MX_WITH_FIXING_PINS"))
    )
    (comp (ref "SW61")
      (value "G6")
      (footprint "eagle-import:MX1A-XXNW")
      (libsource (lib "eagle-import") (part "CHERRY_MX_WITH_FIXING_PINS"))
    )
    (comp (ref "SW62")
      (value "G8")
      (footprint "eagle-import:MX1A-XXNW")
      (libsource (lib "eagle-import") (part "CHERRY_MX_WITH_FIXING_PINS"))
    )
    (comp (ref "SW63")
      (value "G7")
      (footprint "eagle-import:MX1A-XXNW")
      (libsource (lib "eagle-import") (part "CHERRY_MX_WITH_FIXING_PINS"))
    )
    (comp (ref "SW64")
      (value "F8")
      (footprint "eagle-import:MX1A-XXNW")
      (libsource (lib "eagle-import") (part "CHERRY_MX_WITH_FIXING_PINS"))
    )
    (comp (ref "SW65")
      (value "F7")
      (footprint "eagle-import:MX1A-XXNW")
      (libsource (lib "eagle-import") (part "CHERRY_MX_WITH_FIXING_PINS"))
    )
    (comp (ref "SW66")
      (value "H5")
      (footprint "eagle-import:MX1A-XXNW")
      (libsource (lib "eagle-import") (part "CHERRY_MX_WITH_FIXING_PINS"))
    )
    (comp (ref "SW67")
      (value "H6")
      (footprint "eagle-import:MX1A-XXNW")
      (libsource (lib "eagle-import") (part "CHERRY_MX_WITH_FIXING_PINS"))
    )
    (comp (ref "SW68")
      (value "H7")
      (footprint "eagle-import:MX1A-XXNW")
      (libsource (lib "eagle-import") (part "CHERRY_MX_WITH_FIXING_PINS"))
    )
    (comp (ref "SW69")
      (value "H8")
      (footprint "eagle-import:MX1A-XXNW")
      (libsource (lib "eagle-import") (part "CHERRY_MX_WITH_FIXING_PINS"))
    )
    (comp (ref "SW70")
      (value "Shift")
      (footprint "eagle-import:MX1A-XXNW")
      (libsource (lib "eagle-import") (part "CHERRY_MX_WITH_FIXING_PINS"))
    )
    (comp (ref "SW71")
      (value "Act 1")
      (footprint "eagle-import:MX1A-XXNW")
      (libsource (lib "eagle-import") (part "CHERRY_MX_WITH_FIXING_PINS"))
    )
    (comp (ref "SW72")
      (value "Act 2")
      (footprint "eagle-import:MX1A-XXNW")
      (libsource (lib "eagle-import") (part "CHERRY_MX_WITH_FIXING_PINS"))
    )
    (comp (ref "SW73")
      (value "Act 3")
      (footprint "eagle-import:MX1A-XXNW")
      (libsource (lib "eagle-import") (part "CHERRY_MX_WITH_FIXING_PINS"))
    )
    (comp (ref "SW74")
      (value "Row A")
      (footprint "eagle-import:MX1A-XXNW")
      (libsource (lib "eagle-import") (part "CHERRY_MX_WITH_FIXING_PINS"))
    )
    (comp (ref "SW75")
      (value "Act 4")
      (footprint "eagle-import:MX1A-XXNW")
      (libsource (lib "eagle-import") (part "CHERRY_MX_WITH_FIXING_PINS"))
    )
    (comp (ref "SW76")
      (value "Act 5")
      (footprint "eagle-import:MX1A-XXNW")
      (libsource (lib "eagle-import") (part "CHERRY_MX_WITH_FIXING_PINS"))
    )
    (comp (ref "SW77")
      (value "Act 6")
      (footprint "eagle-import:MX1A-XXNW")
      (libsource (lib "eagle-import") (part "CHERRY_MX_WITH_FIXING_PINS"))
    )
    (comp (ref "SW78")
      (value "Row B")
      (footprint "eagle-import:MX1A-XXNW")
      (libsource (lib "eagle-import") (part "CHERRY_MX_WITH_FIXING_PINS"))
    )
    (comp (ref "SW79")
      (value "Act 7")
      (footprint "eagle-import:MX1A-XXNW")
      (libsource (lib "eagle-import") (part "CHERRY_MX_WITH_FIXING_PINS"))
    )
    (comp (ref "SW80")
      (value "Row C")
      (footprint "eagle-import:MX1A-XXNW")
      (libsource (lib "eagle-import") (part "CHERRY_MX_WITH_FIXING_PINS"))
    )
    (comp (ref "SW81")
      (value "Act 8")
      (footprint "eagle-import:MX1A-XXNW")
      (libsource (lib "eagle-import") (part "CHERRY_MX_WITH_FIXING_PINS"))
    )
    (comp (ref "SW82")
      (value "X")
      (footprint "eagle-import:MX1A-XXNW")
      (libsource (lib "eagle-import") (part "CHERRY_MX_WITH_FIXING_PINS"))
    )
    (comp (ref "SW83")
      (value "C3")
      (footprint "eagle-import:MX1A-XXNW")
      (libsource (lib "eagle-import") (part "CHERRY_MX_WITH_FIXING_PINS"))
    )
    (comp (ref "SW87")
      (value "Row D")
      (footprint "eagle-import:MX1A-XXNW")
      (libsource (lib "eagle-import") (part "CHERRY_MX_WITH_FIXING_PINS"))
    )
    (comp (ref "SW88")
      (value "B4")
      (footprint "eagle-import:MX1A-XXNW")
      (libsource (lib "eagle-import") (part "CHERRY_MX_WITH_FIXING_PINS"))
    )
    (comp (ref "SW90")
      (value "B3")
      (footprint "eagle-import:MX1A-XXNW")
      (libsource (lib "eagle-import") (part "CHERRY_MX_WITH_FIXING_PINS"))
    )
    (comp (ref "SW93")
      (value "Row E")
      (footprint "eagle-import:MX1A-XXNW")
      (libsource (lib "eagle-import") (part "CHERRY_MX_WITH_FIXING_PINS"))
    )
    (comp (ref "SW97")
      (value "Row F")
      (footprint "eagle-import:MX1A-XXNW")
      (libsource (lib "eagle-import") (part "CHERRY_MX_WITH_FIXING_PINS"))
    )
    (comp (ref "SW99")
      (value "Row G")
      (footprint "eagle-import:MX1A-XXNW")
      (libsource (lib "eagle-import") (part "CHERRY_MX_WITH_FIXING_PINS"))
    )
    (comp (ref "SW105")
      (value "Row H")
      (footprint "eagle-import:MX1A-XXNW")
      (libsource (lib "eagle-import") (part "CHERRY_MX_WITH_FIXING_PINS"))
    )
    (comp (ref "U$60")
      (value "RESONATOR")
      (footprint "eagle-import:16MHZXTAL")
      (libsource (lib "eagle-import") (part "RESONATOR"))
    )
    (comp (ref "U1")
      (value "ATMEGA32U4-MU")
      (footprint "eagle-import:QFN44")
      (libsource (lib "eagle-import") (part "ATMEGA32U4-MU"))
    )
  )
  (nets
    (net (code "1") (name "/COL1") (class "Default")
      (node (ref "D1") (pin "A") (pinfunction "A_A") (pintype "passive"))
      (node (ref "D12") (pin "A") (pinfunction "A_A") (pintype "passive"))
      (node (ref "D15") (pin "A") (pinfunction "A_A") (pintype "passive"))
      (node (ref "D37") (pin "A") (pinfunction "A_A") (pintype "passive"))
      (node (ref "D40") (pin "A") (pinfunction "A_A") (pintype "passive"))
      (node (ref "D44") (pin "A") (pinfunction "A_A") (pintype "passive"))
      (node (ref "D49") (pin "A") (pinfunction "A_A") (pintype "passive"))
      (node (ref "D5") (pin "A") (pinfunction "A_A") (pintype "passive"))
      (node (ref "D74") (pin "A") (pinfunction "A_A") (pintype "passive"))
      (node (ref "D8") (pin "A") (pinfunction "A_A") (pintype "passive"))
      (node (ref "U1") (pin "22") (pinfunction "PD5(XCLK1/~{CTS})_22") (pintype "bidirectional"))
    )
    (net (code "2") (name "/COL2") (class "Default")
      (node (ref "D13") (pin "A") (pinfunction "A_A") (pintype "passive"))
      (node (ref "D16") (pin "A") (pinfunction "A_A") (pintype "passive"))
      (node (ref "D2") (pin "A") (pinfunction "A_A") (pintype "passive"))
      (node (ref "D38") (pin "A") (pinfunction "A_A") (pintype "passive"))
      (node (ref "D41") (pin "A") (pinfunction "A_A") (pintype "passive"))
      (node (ref "D45") (pin "A") (pinfunction "A_A") (pintype "passive"))
      (node (ref "D50") (pin "A") (pinfunction "A_A") (pintype "passive"))
      (node (ref "D6") (pin "A") (pinfunction "A_A") (pintype "passive"))
      (node (ref "D75") (pin "A") (pinfunction "A_A") (pintype "passive"))
      (node (ref "D9") (pin "A") (pinfunction "A_A") (pintype "passive"))
      (node (ref "U1") (pin "36") (pinfunction "PF7(ADC7/TDI)_36") (pintype "bidirectional"))
    )
    (net (code "3") (name "/COL3") (class "Default")
      (node (ref "D10") (pin "A") (pinfunction "A_A") (pintype "passive"))
      (node (ref "D14") (pin "A") (pinfunction "A_A") (pintype "passive"))
      (node (ref "D3") (pin "A") (pinfunction "A_A") (pintype "passive"))
      (node (ref "D39") (pin "A") (pinfunction "A_A") (pintype "passive"))
      (node (ref "D42") (pin "A") (pinfunction "A_A") (pintype "passive"))
      (node (ref "D46") (pin "A") (pinfunction "A_A") (pintype "passive"))
      (node (ref "D51") (pin "A") (pinfunction "A_A") (pintype "passive"))
      (node (ref "D53") (pin "A") (pinfunction "A_A") (pintype "passive"))
      (node (ref "D7") (pin "A") (pinfunction "A_A") (pintype "passive"))
      (node (ref "D76") (pin "A") (pinfunction "A_A") (pintype "passive"))
      (node (ref "U1") (pin "19") (pinfunction "PD1(SDA/INT1)_19") (pintype "bidirectional"))
    )
    (net (code "4") (name "/COL4") (class "Default")
      (node (ref "D11") (pin "A") (pinfunction "A_A") (pintype "passive"))
      (node (ref "D19") (pin "A") (pinfunction "A_A") (pintype "passive"))
      (node (ref "D20") (pin "A") (pinfunction "A_A") (pintype "passive"))
      (node (ref "D4") (pin "A") (pinfunction "A_A") (pintype "passive"))
      (node (ref "D43") (pin "A") (pinfunction "A_A") (pintype "passive"))
      (node (ref "D47") (pin "A") (pinfunction "A_A") (pintype "passive"))
      (node (ref "D48") (pin "A") (pinfunction "A_A") (pintype "passive"))
      (node (ref "D52") (pin "A") (pinfunction "A_A") (pintype "passive"))
      (node (ref "D54") (pin "A") (pinfunction "A_A") (pintype "passive"))
      (node (ref "D78") (pin "A") (pinfunction "A_A") (pintype "passive"))
      (node (ref "U1") (pin "18") (pinfunction "PD0(OC0B/SCL/INT0)_18") (pintype "bidirectional"))
    )
    (net (code "5") (name "/COL5") (class "Default")
      (node (ref "D17") (pin "A") (pinfunction "A_A") (pintype "passive"))
      (node (ref "D23") (pin "A") (pinfunction "A_A") (pintype "passive"))
      (node (ref "D26") (pin "A") (pinfunction "A_A") (pintype "passive"))
      (node (ref "D30") (pin "A") (pinfunction "A_A") (pintype "passive"))
      (node (ref "D35") (pin "A") (pinfunction "A_A") (pintype "passive"))
      (node (ref "D55") (pin "A") (pinfunction "A_A") (pintype "passive"))
      (node (ref "D58") (pin "A") (pinfunction "A_A") (pintype "passive"))
      (node (ref "D62") (pin "A") (pinfunction "A_A") (pintype "passive"))
      (node (ref "D67") (pin "A") (pinfunction "A_A") (pintype "passive"))
      (node (ref "D79") (pin "A") (pinfunction "A_A") (pintype "passive"))
      (node (ref "U1") (pin "41") (pinfunction "PF0(ADC0)_41") (pintype "bidirectional"))
    )
    (net (code "6") (name "/COL6") (class "Default")
      (node (ref "D18") (pin "A") (pinfunction "A_A") (pintype "passive"))
      (node (ref "D24") (pin "A") (pinfunction "A_A") (pintype "passive"))
      (node (ref "D27") (pin "A") (pinfunction "A_A") (pintype "passive"))
      (node (ref "D31") (pin "A") (pinfunction "A_A") (pintype "passive"))
      (node (ref "D36") (pin "A") (pinfunction "A_A") (pintype "passive"))
      (node (ref "D56") (pin "A") (pinfunction "A_A") (pintype "passive"))
      (node (ref "D59") (pin "A") (pinfunction "A_A") (pintype "passive"))
      (node (ref "D63") (pin "A") (pinfunction "A_A") (pintype "passive"))
      (node (ref "D68") (pin "A") (pinfunction "A_A") (pintype "passive"))
      (node (ref "D81") (pin "A") (pinfunction "A_A") (pintype "passive"))
      (node (ref "U1") (pin "40") (pinfunction "PF1(ADC1)_40") (pintype "bidirectional"))
    )
    (net (code "7") (name "/COL7") (class "Default")
      (node (ref "D21") (pin "A") (pinfunction "A_A") (pintype "passive"))
      (node (ref "D25") (pin "A") (pinfunction "A_A") (pintype "passive"))
      (node (ref "D28") (pin "A") (pinfunction "A_A") (pintype "passive"))
      (node (ref "D32") (pin "A") (pinfunction "A_A") (pintype "passive"))
      (node (ref "D57") (pin "A") (pinfunction "A_A") (pintype "passive"))
      (node (ref "D60") (pin "A") (pinfunction "A_A") (pintype "passive"))
      (node (ref "D64") (pin "A") (pinfunction "A_A") (pintype "passive"))
      (node (ref "D69") (pin "A") (pinfunction "A_A") (pintype "passive"))
      (node (ref "D71") (pin "A") (pinfunction "A_A") (pintype "passive"))
      (node (ref "D82") (pin "A") (pinfunction "A_A") (pintype "passive"))
      (node (ref "U1") (pin "39") (pinfunction "PF4(ADC4/TCK)_39") (pintype "bidirectional"))
    )
    (net (code "8") (name "/COL8") (class "Default")
      (node (ref "D22") (pin "A") (pinfunction "A_A") (pintype "passive"))
      (node (ref "D29") (pin "A") (pinfunction "A_A") (pintype "passive"))
      (node (ref "D33") (pin "A") (pinfunction "A_A") (pintype "passive"))
      (node (ref "D34") (pin "A") (pinfunction "A_A") (pintype "passive"))
      (node (ref "D61") (pin "A") (pinfunction "A_A") (pintype "passive"))
      (node (ref "D65") (pin "A") (pinfunction "A_A") (pintype "passive"))
      (node (ref "D66") (pin "A") (pinfunction "A_A") (pintype "passive"))
      (node (ref "D70") (pin "A") (pinfunction "A_A") (pintype "passive"))
      (node (ref "D72") (pin "A") (pinfunction "A_A") (pintype "passive"))
      (node (ref "D83") (pin "A") (pinfunction "A_A") (pintype "passive"))
      (node (ref "U1") (pin "38") (pinfunction "PF5(ADC5/TMS)_38") (pintype "bidirectional"))
    )
    (net (code "9") (name "/COL9") (class "Default")
      (node (ref "D103") (pin "A") (pinfunction "A_A") (pintype "passive"))
      (node (ref "D73") (pin "A") (pinfunction "A_A") (pintype "passive"))
      (node (ref "D77") (pin "A") (pinfunction "A_A") (pintype "passive"))
      (node (ref "D80") (pin "A") (pinfunction "A_A") (pintype "passive"))
      (node (ref "D84") (pin "A") (pinfunction "A_A") (pintype "passive"))
      (node (ref "D85") (pin "A") (pinfunction "A_A") (pintype "passive"))
      (node (ref "D89") (pin "A") (pinfunction "A_A") (pintype "passive"))
      (node (ref "D91") (pin "A") (pinfunction "A_A") (pintype "passive"))
      (node (ref "D94") (pin "A") (pinfunction "A_A") (pintype "passive"))
      (node (ref "D98") (pin "A") (pinfunction "A_A") (pintype "passive"))
      (node (ref "U1") (pin "37") (pinfunction "PF6(ADC6/TDO)_37") (pintype "bidirectional"))
    )
    (net (code "10") (name "/DM") (class "Default")
      (node (ref "J1") (pin "2") (pinfunction "DM_2") (pintype "bidirectional"))
      (node (ref "R7") (pin "2") (pinfunction "2_2") (pintype "bidirectional"))
    )
    (net (code "11") (name "/DP") (class "Default")
      (node (ref "J1") (pin "3") (pinfunction "DP_3") (pintype "bidirectional"))
      (node (ref "R8") (pin "2") (pinfunction "2_2") (pintype "bidirectional"))
    )
    (net (code "12") (name "/LED") (class "Default")
      (node (ref "LED91") (pin "4") (pinfunction "DI_4") (pintype "input"))
      (node (ref "U1") (pin "27") (pinfunction "PD7(T0/OC4D/ADC10)_27") (pintype "bidirectional"))
    )
    (net (code "13") (name "/MISO") (class "Default")
      (node (ref "ISP1") (pin "1") (pinfunction "MISO_1") (pintype "input"))
      (node (ref "U1") (pin "11") (pinfunction "PB3(PD0/PCINT3/MISO)_11") (pintype "bidirectional"))
    )
    (net (code "14") (name "/MOSI") (class "Default")
      (node (ref "ISP1") (pin "4") (pinfunction "MOSI_4") (pintype "output"))
      (node (ref "U1") (pin "10") (pinfunction "PB2(PDI/PCINT2/MOSI)_10") (pintype "bidirectional"))
    )
    (net (code "15") (name "/RESET") (class "Default")
      (node (ref "ISP1") (pin "5") (pinfunction "RST_5") (pintype "output"))
      (node (ref "R9") (pin "1") (pinfunction "1_1") (pintype "bidirectional"))
      (node (ref "U1") (pin "13") (pinfunction "~{RESET}_13") (pintype "bidirectional"))
    )
    (net (code "16") (name "/ROW1") (class "Default")
      (node (ref "SW3") (pin "2") (pinfunction "2_2") (pintype "passive"))
      (node (ref "SW4") (pin "2") (pinfunction "2_2") (pintype "passive"))
      (node (ref "SW46") (pin "2") (pinfunction "2_2") (pintype "passive"))
      (node (ref "SW47") (pin "2") (pinfunction "2_2") (pintype "passive"))
      (node (ref "SW48") (pin "2") (pinfunction "2_2") (pintype "passive"))
      (node (ref "SW49") (pin "2") (pinfunction "2_2") (pintype "passive"))
      (node (ref "SW5") (pin "2") (pinfunction "2_2") (pintype "passive"))
      (node (ref "SW6") (pin "2") (pinfunction "2_2") (pintype "passive"))
      (node (ref "SW70") (pin "2") (pinfunction "2_2") (pintype "passive"))
      (node (ref "U1") (pin "8") (pinfunction "PB0(SS/PCINT0)_8") (pintype "bidirectional"))
    )
    (net (code "17") (name "/ROW2") (class "Default")
      (node (ref "SW10") (pin "2") (pinfunction "2_2") (pintype "passive"))
      (node (ref "SW51") (pin "2") (pinfunction "2_2") (pintype "passive"))
      (node (ref "SW52") (pin "2") (pinfunction "2_2") (pintype "passive"))
      (node (ref "SW53") (pin "2") (pinfunction "2_2") (pintype "passive"))
      (node (ref "SW54") (pin "2") (pinfunction "2_2") (pintype "passive"))
      (node (ref "SW7") (pin "2") (pinfunction "2_2") (pintype "passive"))
      (node (ref "SW74") (pin "2") (pinfunction "2_2") (pintype "passive"))
      (node (ref "SW8") (pin "2") (pinfunction "2_2") (pintype "passive"))
      (node (ref "SW9") (pin "2") (pinfunction "2_2") (pintype "passive"))
      (node (ref "U1") (pin "32") (pinfunction "PC7(ICP3/CLK0/OC4A)_32") (pintype "bidirectional"))
    )
    (net (code "18") (name "/ROW3") (class "Default")
      (node (ref "SW11") (pin "2") (pinfunction "2_2") (pintype "passive"))
      (node (ref "SW12") (pin "2") (pinfunction "2_2") (pintype "passive"))
      (node (ref "SW17") (pin "2") (pinfunction "2_2") (pintype "passive"))
      (node (ref "SW18") (pin "2") (pinfunction "2_2") (pintype "passive"))
      (node (ref "SW55") (pin "2") (pinfunction "2_2") (pintype "passive"))
      (node (ref "SW56") (pin "2") (pinfunction "2_2") (pintype "passive"))
      (node (ref "SW78") (pin "2") (pinfunction "2_2") (pintype "passive"))
      (node (ref "SW88") (pin "2") (pinfunction "2_2") (pintype "passive"))
      (node (ref "SW90") (pin "2") (pinfunction "2_2") (pintype "passive"))
      (node (ref "U1") (pin "26") (pinfunction "PD6(T1/ADC9/~{OC4D})_26") (pintype "bidirectional"))
    )
    (net (code "19") (name "/ROW4") (class "Default")
      (node (ref "SW13") (pin "2") (pinfunction "2_2") (pintype "passive"))
      (node (ref "SW14") (pin "2") (pinfunction "2_2") (pintype "passive"))
      (node (ref "SW15") (pin "2") (pinfunction "2_2") (pintype "passive"))
      (node (ref "SW16") (pin "2") (pinfunction "2_2") (pintype "passive"))
      (node (ref "SW58") (pin "2") (pinfunction "2_2") (pintype "passive"))
      (node (ref "SW59") (pin "2") (pinfunction "2_2") (pintype "passive"))
      (node (ref "SW60") (pin "2") (pinfunction "2_2") (pintype "passive"))
      (node (ref "SW80") (pin "2") (pinfunction "2_2") (pintype "passive"))
      (node (ref "SW83") (pin "2") (pinfunction "2_2") (pintype "passive"))
      (node (ref "U1") (pin "12") (pinfunction "PB7(PCINT7/OC0A/OC1C/~{RTS})_12") (pintype "bidirectional"))
    )
    (net (code "20") (name "/ROW5") (class "Default")
      (node (ref "SW1") (pin "2") (pinfunction "2_2") (pintype "passive"))
      (node (ref "SW19") (pin "2") (pinfunction "2_2") (pintype "passive"))
      (node (ref "SW2") (pin "2") (pinfunction "2_2") (pintype "passive"))
      (node (ref "SW20") (pin "2") (pinfunction "2_2") (pintype "passive"))
      (node (ref "SW21") (pin "2") (pinfunction "2_2") (pintype "passive"))
      (node (ref "SW22") (pin "2") (pinfunction "2_2") (pintype "passive"))
      (node (ref "SW39") (pin "2") (pinfunction "2_2") (pintype "passive"))
      (node (ref "SW40") (pin "2") (pinfunction "2_2") (pintype "passive"))
      (node (ref "SW87") (pin "2") (pinfunction "2_2") (pintype "passive"))
      (node (ref "U1") (pin "30") (pinfunction "PB6(PCINT6/OC1B/OC4B/ADC13)_30") (pintype "bidirectional"))
    )
    (net (code "21") (name "/ROW6") (class "Default")
      (node (ref "SW23") (pin "2") (pinfunction "2_2") (pintype "passive"))
      (node (ref "SW24") (pin "2") (pinfunction "2_2") (pintype "passive"))
      (node (ref "SW25") (pin "2") (pinfunction "2_2") (pintype "passive"))
      (node (ref "SW26") (pin "2") (pinfunction "2_2") (pintype "passive"))
      (node (ref "SW41") (pin "2") (pinfunction "2_2") (pintype "passive"))
      (node (ref "SW42") (pin "2") (pinfunction "2_2") (pintype "passive"))
      (node (ref "SW43") (pin "2") (pinfunction "2_2") (pintype "passive"))
      (node (ref "SW44") (pin "2") (pinfunction "2_2") (pintype "passive"))
      (node (ref "SW93") (pin "2") (pinfunction "2_2") (pintype "passive"))
      (node (ref "U1") (pin "29") (pinfunction "PB5(PCINT5/OC1A/ADC12/~{OC4B})_29") (pintype "bidirectional"))
    )
    (net (code "22") (name "/ROW7") (class "Default")
      (node (ref "SW27") (pin "2") (pinfunction "2_2") (pintype "passive"))
      (node (ref "SW28") (pin "2") (pinfunction "2_2") (pintype "passive"))
      (node (ref "SW33") (pin "2") (pinfunction "2_2") (pintype "passive"))
      (node (ref "SW34") (pin "2") (pinfunction "2_2") (pintype "passive"))
      (node (ref "SW45") (pin "2") (pinfunction "2_2") (pintype "passive"))
      (node (ref "SW50") (pin "2") (pinfunction "2_2") (pintype "passive"))
      (node (ref "SW64") (pin "2") (pinfunction "2_2") (pintype "passive"))
      (node (ref "SW65") (pin "2") (pinfunction "2_2") (pintype "passive"))
      (node (ref "SW97") (pin "2") (pinfunction "2_2") (pintype "passive"))
      (node (ref "U1") (pin "28") (pinfunction "PB4(PCINT4/ADC11)_28") (pintype "bidirectional"))
    )
    (net (code "23") (name "/ROW8") (class "Default")
      (node (ref "SW29") (pin "2") (pinfunction "2_2") (pintype "passive"))
      (node (ref "SW30") (pin "2") (pinfunction "2_2") (pintype "passive"))
      (node (ref "SW31") (pin "2") (pinfunction "2_2") (pintype "passive"))
      (node (ref "SW32") (pin "2") (pinfunction "2_2") (pintype "passive"))
      (node (ref "SW57") (pin "2") (pinfunction "2_2") (pintype "passive"))
      (node (ref "SW61") (pin "2") (pinfunction "2_2") (pintype "passive"))
      (node (ref "SW62") (pin "2") (pinfunction "2_2") (pintype "passive"))
      (node (ref "SW63") (pin "2") (pinfunction "2_2") (pintype "passive"))
      (node (ref "SW99") (pin "2") (pinfunction "2_2") (pintype "passive"))
      (node (ref "U1") (pin "1") (pinfunction "PE6(INT.6/AIN0)_1") (pintype "bidirectional"))
    )
    (net (code "24") (name "/ROW9") (class "Default")
      (node (ref "SW105") (pin "2") (pinfunction "2_2") (pintype "passive"))
      (node (ref "SW35") (pin "2") (pinfunction "2_2") (pintype "passive"))
      (node (ref "SW36") (pin "2") (pinfunction "2_2") (pintype "passive"))
      (node (ref "SW37") (pin "2") (pinfunction "2_2") (pintype "passive"))
      (node (ref "SW38") (pin "2") (pinfunction "2_2") (pintype "passive"))
      (node (ref "SW66") (pin "2") (pinfunction "2_2") (pintype "passive"))
      (node (ref "SW67") (pin "2") (pinfunction "2_2") (pintype "passive"))
      (node (ref "SW68") (pin "2") (pinfunction "2_2") (pintype "passive"))
      (node (ref "SW69") (pin "2") (pinfunction "2_2") (pintype "passive"))
      (node (ref "U1") (pin "31") (pinfunction "PC6(OC3A/~{OC4A})_31") (pintype "bidirectional"))
    )
    (net (code "25") (name "/ROW10") (class "Default")
      (node (ref "SW71") (pin "2") (pinfunction "2_2") (pintype "passive"))
      (node (ref "SW72") (pin "2") (pinfunction "2_2") (pintype "passive"))
      (node (ref "SW73") (pin "2") (pinfunction "2_2") (pintype "passive"))
      (node (ref "SW75") (pin "2") (pinfunction "2_2") (pintype "passive"))
      (node (ref "SW76") (pin "2") (pinfunction "2_2") (pintype "passive"))
      (node (ref "SW77") (pin "2") (pinfunction "2_2") (pintype "passive"))
      (node (ref "SW79") (pin "2") (pinfunction "2_2") (pintype "passive"))
      (node (ref "SW81") (pin "2") (pinfunction "2_2") (pintype "passive"))
      (node (ref "SW82") (pin "2") (pinfunction "2_2") (pintype "passive"))
      (node (ref "U1") (pin "25") (pinfunction "PD4(ICP1/ADC8)_25") (pintype "bidirectional"))
    )
    (net (code "26") (name "/RX") (class "Default")
      (node (ref "JP2") (pin "2") (pinfunction "2_2") (pintype "passive"))
      (node (ref "U1") (pin "20") (pinfunction "PD2(RXD1/INT2)_20") (pintype "bidirectional"))
    )
    (net (code "27") (name "/SCLK") (class "Default")
      (node (ref "ISP1") (pin "3") (pinfunction "SCK_3") (pintype "output"))
      (node (ref "U1") (pin "9") (pinfunction "PB1(PCINT1/SCLK)_9") (pintype "bidirectional"))
    )
    (net (code "28") (name "/TX") (class "Default")
      (node (ref "JP2") (pin "3") (pinfunction "3_3") (pintype "passive"))
      (node (ref "U1") (pin "21") (pinfunction "PD3(TXD1/INT3)_21") (pintype "bidirectional"))
    )
    (net (code "29") (name "5V") (class "Default")
      (node (ref "C1") (pin "2") (pinfunction "2_2") (pintype "bidirectional"))
      (node (ref "C2") (pin "2") (pinfunction "2_2") (pintype "bidirectional"))
      (node (ref "C3") (pin "2") (pinfunction "2_2") (pintype "bidirectional"))
      (node (ref "C4") (pin "2") (pinfunction "2_2") (pintype "bidirectional"))
      (node (ref "ISP1") (pin "2") (pinfunction "VCC_2") (pintype "power_in"))
      (node (ref "J1") (pin "1") (pinfunction "VCC_1") (pintype "bidirectional"))
      (node (ref "LED1") (pin "1") (pinfunction "VDD_1") (pintype "power_in"))
      (node (ref "LED10") (pin "1") (pinfunction "VDD_1") (pintype "power_in"))
      (node (ref "LED11") (pin "1") (pinfunction "VDD_1") (pintype "power_in"))
      (node (ref "LED12") (pin "1") (pinfunction "VDD_1") (pintype "power_in"))
      (node (ref "LED13") (pin "1") (pinfunction "VDD_1") (pintype "power_in"))
      (node (ref "LED14") (pin "1") (pinfunction "VDD_1") (pintype "power_in"))
      (node (ref "LED15") (pin "1") (pinfunction "VDD_1") (pintype "power_in"))
      (node (ref "LED16") (pin "1") (pinfunction "VDD_1") (pintype "power_in"))
      (node (ref "LED17") (pin "1") (pinfunction "VDD_1") (pintype "power_in"))
      (node (ref "LED18") (pin "1") (pinfunction "VDD_1") (pintype "power_in"))
      (node (ref "LED19") (pin "1") (pinfunction "VDD_1") (pintype "power_in"))
      (node (ref "LED2") (pin "1") (pinfunction "VDD_1") (pintype "power_in"))
      (node (ref "LED20") (pin "1") (pinfunction "VDD_1") (pintype "power_in"))
      (node (ref "LED21") (pin "1") (pinfunction "VDD_1") (pintype "power_in"))
      (node (ref "LED22") (pin "1") (pinfunction "VDD_1") (pintype "power_in"))
      (node (ref "LED23") (pin "1") (pinfunction "VDD_1") (pintype "power_in"))
      (node (ref "LED24") (pin "1") (pinfunction "VDD_1") (pintype "power_in"))
      (node (ref "LED25") (pin "1") (pinfunction "VDD_1") (pintype "power_in"))
      (node (ref "LED26") (pin "1") (pinfunction "VDD_1") (pintype "power_in"))
      (node (ref "LED27") (pin "1") (pinfunction "VDD_1") (pintype "power_in"))
      (node (ref "LED28") (pin "1") (pinfunction "VDD_1") (pintype "power_in"))
      (node (ref "LED29") (pin "1") (pinfunction "VDD_1") (pintype "power_in"))
      (node (ref "LED3") (pin "1") (pinfunction "VDD_1") (pintype "power_in"))
      (node (ref "LED30") (pin "1") (pinfunction "VDD_1") (pintype "power_in"))
      (node (ref "LED31") (pin "1") (pinfunction "VDD_1") (pintype "power_in"))
      (node (ref "LED32") (pin "1") (pinfunction "VDD_1") (pintype "power_in"))
      (node (ref "LED33") (pin "1") (pinfunction "VDD_1") (pintype "power_in"))
      (node (ref "LED34") (pin "1") (pinfunction "VDD_1") (pintype "power_in"))
      (node (ref "LED35") (pin "1") (pinfunction "VDD_1") (pintype "power_in"))
      (node (ref "LED36") (pin "1") (pinfunction "VDD_1") (pintype "power_in"))
      (node (ref "LED37") (pin "1") (pinfunction "VDD_1") (pintype "power_in"))
      (node (ref "LED38") (pin "1") (pinfunction "VDD_1") (pintype "power_in"))
      (node (ref "LED39") (pin "1") (pinfunction "VDD_1") (pintype "power_in"))
      (node (ref "LED4") (pin "1") (pinfunction "VDD_1") (pintype "power_in"))
      (node (ref "LED40") (pin "1") (pinfunction "VDD_1") (pintype "power_in"))
      (node (ref "LED41") (pin "1") (pinfunction "VDD_1") (pintype "power_in"))
      (node (ref "LED42") (pin "1") (pinfunction "VDD_1") (pintype "power_in"))
      (node (ref "LED43") (pin "1") (pinfunction "VDD_1") (pintype "power_in"))
      (node (ref "LED44") (pin "1") (pinfunction "VDD_1") (pintype "power_in"))
      (node (ref "LED45") (pin "1") (pinfunction "VDD_1") (pintype "power_in"))
      (node (ref "LED46") (pin "1") (pinfunction "VDD_1") (pintype "power_in"))
      (node (ref "LED47") (pin "1") (pinfunction "VDD_1") (pintype "power_in"))
      (node (ref "LED48") (pin "1") (pinfunction "VDD_1") (pintype "power_in"))
      (node (ref "LED49") (pin "1") (pinfunction "VDD_1") (pintype "power_in"))
      (node (ref "LED5") (pin "1") (pinfunction "VDD_1") (pintype "power_in"))
      (node (ref "LED50") (pin "1") (pinfunction "VDD_1") (pintype "power_in"))
      (node (ref "LED51") (pin "1") (pinfunction "VDD_1") (pintype "power_in"))
      (node (ref "LED52") (pin "1") (pinfunction "VDD_1") (pintype "power_in"))
      (node (ref "LED53") (pin "1") (pinfunction "VDD_1") (pintype "power_in"))
      (node (ref "LED54") (pin "1") (pinfunction "VDD_1") (pintype "power_in"))
      (node (ref "LED55") (pin "1") (pinfunction "VDD_1") (pintype "power_in"))
      (node (ref "LED56") (pin "1") (pinfunction "VDD_1") (pintype "power_in"))
      (node (ref "LED57") (pin "1") (pinfunction "VDD_1") (pintype "power_in"))
      (node (ref "LED58") (pin "1") (pinfunction "VDD_1") (pintype "power_in"))
      (node (ref "LED59") (pin "1") (pinfunction "VDD_1") (pintype "power_in"))
      (node (ref "LED6") (pin "1") (pinfunction "VDD_1") (pintype "power_in"))
      (node (ref "LED60") (pin "1") (pinfunction "VDD_1") (pintype "power_in"))
      (node (ref "LED61") (pin "1") (pinfunction "VDD_1") (pintype "power_in"))
      (node (ref "LED62") (pin "1") (pinfunction "VDD_1") (pintype "power_in"))
      (node (ref "LED63") (pin "1") (pinfunction "VDD_1") (pintype "power_in"))
      (node (ref "LED64") (pin "1") (pinfunction "VDD_1") (pintype "power_in"))
      (node (ref "LED65") (pin "1") (pinfunction "VDD_1") (pintype "power_in"))
      (node (ref "LED66") (pin "1") (pinfunction "VDD_1") (pintype "power_in"))
      (node (ref "LED67") (pin "1") (pinfunction "VDD_1") (pintype "power_in"))
      (node (ref "LED68") (pin "1") (pinfunction "VDD_1") (pintype "power_in"))
      (node (ref "LED69") (pin "1") (pinfunction "VDD_1") (pintype "power_in"))
      (node (ref "LED7") (pin "1") (pinfunction "VDD_1") (pintype "power_in"))
      (node (ref "LED70") (pin "1") (pinfunction "VDD_1") (pintype "power_in"))
      (node (ref "LED71") (pin "1") (pinfunction "VDD_1") (pintype "power_in"))
      (node (ref "LED72") (pin "1") (pinfunction "VDD_1") (pintype "power_in"))
      (node (ref "LED73") (pin "1") (pinfunction "VDD_1") (pintype "power_in"))
      (node (ref "LED74") (pin "1") (pinfunction "VDD_1") (pintype "power_in"))
      (node (ref "LED75") (pin "1") (pinfunction "VDD_1") (pintype "power_in"))
      (node (ref "LED76") (pin "1") (pinfunction "VDD_1") (pintype "power_in"))
      (node (ref "LED77") (pin "1") (pinfunction "VDD_1") (pintype "power_in"))
      (node (ref "LED78") (pin "1") (pinfunction "VDD_1") (pintype "power_in"))
      (node (ref "LED79") (pin "1") (pinfunction "VDD_1") (pintype "power_in"))
      (node (ref "LED8") (pin "1") (pinfunction "VDD_1") (pintype "power_in"))
      (node (ref "LED80") (pin "1") (pinfunction "VDD_1") (pintype "power_in"))
      (node (ref "LED81") (pin "1") (pinfunction "VDD_1") (pintype "power_in"))
      (node (ref "LED82") (pin "1") (pinfunction "VDD_1") (pintype "power_in"))
      (node (ref "LED83") (pin "1") (pinfunction "VDD_1") (pintype "power_in"))
      (node (ref "LED84") (pin "1") (pinfunction "VDD_1") (pintype "power_in"))
      (node (ref "LED85") (pin "1") (pinfunction "VDD_1") (pintype "power_in"))
      (node (ref "LED86") (pin "1") (pinfunction "VDD_1") (pintype "power_in"))
      (node (ref "LED87") (pin "1") (pinfunction "VDD_1") (pintype "power_in"))
      (node (ref "LED88") (pin "1") (pinfunction "VDD_1") (pintype "power_in"))
      (node (ref "LED89") (pin "1") (pinfunction "VDD_1") (pintype "power_in"))
      (node (ref "LED9") (pin "1") (pinfunction "VDD_1") (pintype "power_in"))
      (node (ref "LED90") (pin "1") (pinfunction "VDD_1") (pintype "power_in"))
      (node (ref "LED91") (pin "1") (pinfunction "VDD_1") (pintype "power_in"))
      (node (ref "LED92") (pin "1") (pinfunction "VDD_1") (pintype "power_in"))
      (node (ref "LED93") (pin "1") (pinfunction "VDD_1") (pintype "power_in"))
      (node (ref "LED94") (pin "1") (pinfunction "VDD_1") (pintype "power_in"))
      (node (ref "LED95") (pin "1") (pinfunction "VDD_1") (pintype "power_in"))
      (node (ref "LED96") (pin "1") (pinfunction "VDD_1") (pintype "power_in"))
      (node (ref "LED97") (pin "1") (pinfunction "VDD_1") (pintype "power_in"))
      (node (ref "LED98") (pin "1") (pinfunction "VDD_1") (pintype "power_in"))
      (node (ref "LED99") (pin "1") (pinfunction "VDD_1") (pintype "power_in"))
      (node (ref "R9") (pin "2") (pinfunction "2_2") (pintype "bidirectional"))
      (node (ref "U1") (pin "14") (pinfunction "VCC_14") (pintype "bidirectional"))
      (node (ref "U1") (pin "2") (pinfunction "UVCC_2") (pintype "bidirectional"))
      (node (ref "U1") (pin "24") (pinfunction "AVCC_24") (pintype "bidirectional"))
      (node (ref "U1") (pin "34") (pinfunction "VCC_34") (pintype "bidirectional"))
      (node (ref "U1") (pin "44") (pinfunction "AVCC_44") (pintype "bidirectional"))
      (node (ref "U1") (pin "7") (pinfunction "VBUS_7") (pintype "bidirectional"))
    )
    (net (code "30") (name "GND") (class "Default")
      (node (ref "C1") (pin "1") (pinfunction "1_1") (pintype "bidirectional"))
      (node (ref "C13") (pin "2") (pinfunction "2_2") (pintype "bidirectional"))
      (node (ref "C14") (pin "2") (pinfunction "2_2") (pintype "bidirectional"))
      (node (ref "C15") (pin "2") (pinfunction "2_2") (pintype "bidirectional"))
      (node (ref "C16") (pin "2") (pinfunction "2_2") (pintype "bidirectional"))
      (node (ref "C2") (pin "1") (pinfunction "1_1") (pintype "bidirectional"))
      (node (ref "C3") (pin "1") (pinfunction "1_1") (pintype "bidirectional"))
      (node (ref "C4") (pin "1") (pinfunction "1_1") (pintype "bidirectional"))
      (node (ref "ISP1") (pin "6") (pinfunction "GND_6") (pintype "power_in"))
      (node (ref "J1") (pin "5") (pinfunction "GND_5") (pintype "bidirectional"))
      (node (ref "J1") (pin "GND@1") (pinfunction "GND_GND@1") (pintype "bidirectional"))
      (node (ref "J1") (pin "GND@2") (pinfunction "GND_GND@2") (pintype "bidirectional"))
      (node (ref "J1") (pin "GND@3") (pinfunction "GND_GND@3") (pintype "bidirectional"))
      (node (ref "J1") (pin "GND@4") (pinfunction "GND_GND@4") (pintype "bidirectional"))
      (node (ref "JP2") (pin "1") (pinfunction "1_1") (pintype "passive"))
      (node (ref "LED1") (pin "3") (pinfunction "GND_3") (pintype "power_in"))
      (node (ref "LED10") (pin "3") (pinfunction "GND_3") (pintype "power_in"))
      (node (ref "LED11") (pin "3") (pinfunction "GND_3") (pintype "power_in"))
      (node (ref "LED12") (pin "3") (pinfunction "GND_3") (pintype "power_in"))
      (node (ref "LED13") (pin "3") (pinfunction "GND_3") (pintype "power_in"))
      (node (ref "LED14") (pin "3") (pinfunction "GND_3") (pintype "power_in"))
      (node (ref "LED15") (pin "3") (pinfunction "GND_3") (pintype "power_in"))
      (node (ref "LED16") (pin "3") (pinfunction "GND_3") (pintype "power_in"))
      (node (ref "LED17") (pin "3") (pinfunction "GND_3") (pintype "power_in"))
      (node (ref "LED18") (pin "3") (pinfunction "GND_3") (pintype "power_in"))
      (node (ref "LED19") (pin "3") (pinfunction "GND_3") (pintype "power_in"))
      (node (ref "LED2") (pin "3") (pinfunction "GND_3") (pintype "power_in"))
      (node (ref "LED20") (pin "3") (pinfunction "GND_3") (pintype "power_in"))
      (node (ref "LED21") (pin "3") (pinfunction "GND_3") (pintype "power_in"))
      (node (ref "LED22") (pin "3") (pinfunction "GND_3") (pintype "power_in"))
      (node (ref "LED23") (pin "3") (pinfunction "GND_3") (pintype "power_in"))
      (node (ref "LED24") (pin "3") (pinfunction "GND_3") (pintype "power_in"))
      (node (ref "LED25") (pin "3") (pinfunction "GND_3") (pintype "power_in"))
      (node (ref "LED26") (pin "3") (pinfunction "GND_3") (pintype "power_in"))
      (node (ref "LED27") (pin "3") (pinfunction "GND_3") (pintype "power_in"))
      (node (ref "LED28") (pin "3") (pinfunction "GND_3") (pintype "power_in"))
      (node (ref "LED29") (pin "3") (pinfunction "GND_3") (pintype "power_in"))
      (node (ref "LED3") (pin "3") (pinfunction "GND_3") (pintype "power_in"))
      (node (ref "LED30") (pin "3") (pinfunction "GND_3") (pintype "power_in"))
      (node (ref "LED31") (pin "3") (pinfunction "GND_3") (pintype "power_in"))
      (node (ref "LED32") (pin "3") (pinfunction "GND_3") (pintype "power_in"))
      (node (ref "LED33") (pin "3") (pinfunction "GND_3") (pintype "power_in"))
      (node (ref "LED34") (pin "3") (pinfunction "GND_3") (pintype "power_in"))
      (node (ref "LED35") (pin "3") (pinfunction "GND_3") (pintype "power_in"))
      (node (ref "LED36") (pin "3") (pinfunction "GND_3") (pintype "power_in"))
      (node (ref "LED37") (pin "3") (pinfunction "GND_3") (pintype "power_in"))
      (node (ref "LED38") (pin "3") (pinfunction "GND_3") (pintype "power_in"))
      (node (ref "LED39") (pin "3") (pinfunction "GND_3") (pintype "power_in"))
      (node (ref "LED4") (pin "3") (pinfunction "GND_3") (pintype "power_in"))
      (node (ref "LED40") (pin "3") (pinfunction "GND_3") (pintype "power_in"))
      (node (ref "LED41") (pin "3") (pinfunction "GND_3") (pintype "power_in"))
      (node (ref "LED42") (pin "3") (pinfunction "GND_3") (pintype "power_in"))
      (node (ref "LED43") (pin "3") (pinfunction "GND_3") (pintype "power_in"))
      (node (ref "LED44") (pin "3") (pinfunction "GND_3") (pintype "power_in"))
      (node (ref "LED45") (pin "3") (pinfunction "GND_3") (pintype "power_in"))
      (node (ref "LED46") (pin "3") (pinfunction "GND_3") (pintype "power_in"))
      (node (ref "LED47") (pin "3") (pinfunction "GND_3") (pintype "power_in"))
      (node (ref "LED48") (pin "3") (pinfunction "GND_3") (pintype "power_in"))
      (node (ref "LED49") (pin "3") (pinfunction "GND_3") (pintype "power_in"))
      (node (ref "LED5") (pin "3") (pinfunction "GND_3") (pintype "power_in"))
      (node (ref "LED50") (pin "3") (pinfunction "GND_3") (pintype "power_in"))
      (node (ref "LED51") (pin "3") (pinfunction "GND_3") (pintype "power_in"))
      (node (ref "LED52") (pin "3") (pinfunction "GND_3") (pintype "power_in"))
      (node (ref "LED53") (pin "3") (pinfunction "GND_3") (pintype "power_in"))
      (node (ref "LED54") (pin "3") (pinfunction "GND_3") (pintype "power_in"))
      (node (ref "LED55") (pin "3") (pinfunction "GND_3") (pintype "power_in"))
      (node (ref "LED56") (pin "3") (pinfunction "GND_3") (pintype "power_in"))
      (node (ref "LED57") (pin "3") (pinfunction "GND_3") (pintype "power_in"))
      (node (ref "LED58") (pin "3") (pinfunction "GND_3") (pintype "power_in"))
      (node (ref "LED59") (pin "3") (pinfunction "GND_3") (pintype "power_in"))
      (node (ref "LED6") (pin "3") (pinfunction "GND_3") (pintype "power_in"))
      (node (ref "LED60") (pin "3") (pinfunction "GND_3") (pintype "power_in"))
      (node (ref "LED61") (pin "3") (pinfunction "GND_3") (pintype "power_in"))
      (node (ref "LED62") (pin "3") (pinfunction "GND_3") (pintype "power_in"))
      (node (ref "LED63") (pin "3") (pinfunction "GND_3") (pintype "power_in"))
      (node (ref "LED64") (pin "3") (pinfunction "GND_3") (pintype "power_in"))
      (node (ref "LED65") (pin "3") (pinfunction "GND_3") (pintype "power_in"))
      (node (ref "LED66") (pin "3") (pinfunction "GND_3") (pintype "power_in"))
      (node (ref "LED67") (pin "3") (pinfunction "GND_3") (pintype "power_in"))
      (node (ref "LED68") (pin "3") (pinfunction "GND_3") (pintype "power_in"))
      (node (ref "LED69") (pin "3") (pinfunction "GND_3") (pintype "power_in"))
      (node (ref "LED7") (pin "3") (pinfunction "GND_3") (pintype "power_in"))
      (node (ref "LED70") (pin "3") (pinfunction "GND_3") (pintype "power_in"))
      (node (ref "LED71") (pin "3") (pinfunction "GND_3") (pintype "power_in"))
      (node (ref "LED72") (pin "3") (pinfunction "GND_3") (pintype "power_in"))
      (node (ref "LED73") (pin "3") (pinfunction "GND_3") (pintype "power_in"))
      (node (ref "LED74") (pin "3") (pinfunction "GND_3") (pintype "power_in"))
      (node (ref "LED75") (pin "3") (pinfunction "GND_3") (pintype "power_in"))
      (node (ref "LED76") (pin "3") (pinfunction "GND_3") (pintype "power_in"))
      (node (ref "LED77") (pin "3") (pinfunction "GND_3") (pintype "power_in"))
      (node (ref "LED78") (pin "3") (pinfunction "GND_3") (pintype "power_in"))
      (node (ref "LED79") (pin "3") (pinfunction "GND_3") (pintype "power_in"))
      (node (ref "LED8") (pin "3") (pinfunction "GND_3") (pintype "power_in"))
      (node (ref "LED80") (pin "3") (pinfunction "GND_3") (pintype "power_in"))
      (node (ref "LED81") (pin "3") (pinfunction "GND_3") (pintype "power_in"))
      (node (ref "LED82") (pin "3") (pinfunction "GND_3") (pintype "power_in"))
      (node (ref "LED83") (pin "3") (pinfunction "GND_3") (pintype "power_in"))
      (node (ref "LED84") (pin "3") (pinfunction "GND_3") (pintype "power_in"))
      (node (ref "LED85") (pin "3") (pinfunction "GND_3") (pintype "power_in"))
      (node (ref "LED86") (pin "3") (pinfunction "GND_3") (pintype "power_in"))
      (node (ref "LED87") (pin "3") (pinfunction "GND_3") (pintype "power_in"))
      (node (ref "LED88") (pin "3") (pinfunction "GND_3") (pintype "power_in"))
      (node (ref "LED89") (pin "3") (pinfunction "GND_3") (pintype "power_in"))
      (node (ref "LED9") (pin "3") (pinfunction "GND_3") (pintype "power_in"))
      (node (ref "LED90") (pin "3") (pinfunction "GND_3") (pintype "power_in"))
      (node (ref "LED91") (pin "3") (pinfunction "GND_3") (pintype "power_in"))
      (node (ref "LED92") (pin "3") (pinfunction "GND_3") (pintype "power_in"))
      (node (ref "LED93") (pin "3") (pinfunction "GND_3") (pintype "power_in"))
      (node (ref "LED94") (pin "3") (pinfunction "GND_3") (pintype "power_in"))
      (node (ref "LED95") (pin "3") (pinfunction "GND_3") (pintype "power_in"))
      (node (ref "LED96") (pin "3") (pinfunction "GND_3") (pintype "power_in"))
      (node (ref "LED97") (pin "3") (pinfunction "GND_3") (pintype "power_in"))
      (node (ref "LED98") (pin "3") (pinfunction "GND_3") (pintype "power_in"))
      (node (ref "LED99") (pin "3") (pinfunction "GND_3") (pintype "power_in"))
      (node (ref "U$60") (pin "P$2") (pinfunction "GND_P$2") (pintype "bidirectional"))
      (node (ref "U$60") (pin "P$4") (pinfunction "GND_P$4") (pintype "bidirectional"))
      (node (ref "U1") (pin "15") (pinfunction "GND_15") (pintype "bidirectional"))
      (node (ref "U1") (pin "23") (pinfunction "GND_23") (pintype "bidirectional"))
      (node (ref "U1") (pin "35") (pinfunction "GND_35") (pintype "bidirectional"))
      (node (ref "U1") (pin "43") (pinfunction "GND_43") (pintype "bidirectional"))
      (node (ref "U1") (pin "5") (pinfunction "UGND_5") (pintype "bidirectional"))
      (node (ref "U1") (pin "TAB") (pinfunction "GND_TAB") (pintype "bidirectional"))
    )
    (net (code "31") (name "Net-(D1-PadC)") (class "Default")
      (node (ref "D1") (pin "C") (pinfunction "C_C") (pintype "passive"))
      (node (ref "SW46") (pin "1") (pinfunction "1_1") (pintype "passive"))
    )
    (net (code "32") (name "Net-(D2-PadC)") (class "Default")
      (node (ref "D2") (pin "C") (pinfunction "C_C") (pintype "passive"))
      (node (ref "SW47") (pin "1") (pinfunction "1_1") (pintype "passive"))
    )
    (net (code "33") (name "Net-(D3-PadC)") (class "Default")
      (node (ref "D3") (pin "C") (pinfunction "C_C") (pintype "passive"))
      (node (ref "SW48") (pin "1") (pinfunction "1_1") (pintype "passive"))
    )
    (net (code "34") (name "Net-(D4-PadC)") (class "Default")
      (node (ref "D4") (pin "C") (pinfunction "C_C") (pintype "passive"))
      (node (ref "SW49") (pin "1") (pinfunction "1_1") (pintype "passive"))
    )
    (net (code "35") (name "Net-(D5-PadC)") (class "Default")
      (node (ref "D5") (pin "C") (pinfunction "C_C") (pintype "passive"))
      (node (ref "SW51") (pin "1") (pinfunction "1_1") (pintype "passive"))
    )
    (net (code "36") (name "Net-(D6-PadC)") (class "Default")
      (node (ref "D6") (pin "C") (pinfunction "C_C") (pintype "passive"))
      (node (ref "SW52") (pin "1") (pinfunction "1_1") (pintype "passive"))
    )
    (net (code "37") (name "Net-(D7-PadC)") (class "Default")
      (node (ref "D7") (pin "C") (pinfunction "C_C") (pintype "passive"))
      (node (ref "SW53") (pin "1") (pinfunction "1_1") (pintype "passive"))
    )
    (net (code "38") (name "Net-(D8-PadC)") (class "Default")
      (node (ref "D8") (pin "C") (pinfunction "C_C") (pintype "passive"))
      (node (ref "SW55") (pin "1") (pinfunction "1_1") (pintype "passive"))
    )
    (net (code "39") (name "Net-(D9-PadC)") (class "Default")
      (node (ref "D9") (pin "C") (pinfunction "C_C") (pintype "passive"))
      (node (ref "SW56") (pin "1") (pinfunction "1_1") (pintype "passive"))
    )
    (net (code "40") (name "Net-(D10-PadC)") (class "Default")
      (node (ref "D10") (pin "C") (pinfunction "C_C") (pintype "passive"))
      (node (ref "SW90") (pin "1") (pinfunction "1_1") (pintype "passive"))
    )
    (net (code "41") (name "Net-(D11-PadC)") (class "Default")
      (node (ref "D11") (pin "C") (pinfunction "C_C") (pintype "passive"))
      (node (ref "SW88") (pin "1") (pinfunction "1_1") (pintype "passive"))
    )
    (net (code "42") (name "Net-(D12-PadC)") (class "Default")
      (node (ref "D12") (pin "C") (pinfunction "C_C") (pintype "passive"))
      (node (ref "SW58") (pin "1") (pinfunction "1_1") (pintype "passive"))
    )
    (net (code "43") (name "Net-(D13-PadC)") (class "Default")
      (node (ref "D13") (pin "C") (pinfunction "C_C") (pintype "passive"))
      (node (ref "SW59") (pin "1") (pinfunction "1_1") (pintype "passive"))
    )
    (net (code "44") (name "Net-(D14-PadC)") (class "Default")
      (node (ref "D14") (pin "C") (pinfunction "C_C") (pintype "passive"))
      (node (ref "SW83") (pin "1") (pinfunction "1_1") (pintype "passive"))
    )
    (net (code "45") (name "Net-(D15-PadC)") (class "Default")
      (node (ref "D15") (pin "C") (pinfunction "C_C") (pintype "passive"))
      (node (ref "SW1") (pin "1") (pinfunction "1_1") (pintype "passive"))
    )
    (net (code "46") (name "Net-(D16-PadC)") (class "Default")
      (node (ref "D16") (pin "C") (pinfunction "C_C") (pintype "passive"))
      (node (ref "SW2") (pin "1") (pinfunction "1_1") (pintype "passive"))
    )
    (net (code "47") (name "Net-(D17-PadC)") (class "Default")
      (node (ref "D17") (pin "C") (pinfunction "C_C") (pintype "passive"))
      (node (ref "SW3") (pin "1") (pinfunction "1_1") (pintype "passive"))
    )
    (net (code "48") (name "Net-(D18-PadC)") (class "Default")
      (node (ref "D18") (pin "C") (pinfunction "C_C") (pintype "passive"))
      (node (ref "SW4") (pin "1") (pinfunction "1_1") (pintype "passive"))
    )
    (net (code "49") (name "Net-(D19-PadC)") (class "Default")
      (node (ref "D19") (pin "C") (pinfunction "C_C") (pintype "passive"))
      (node (ref "SW60") (pin "1") (pinfunction "1_1") (pintype "passive"))
    )
    (net (code "50") (name "Net-(D20-PadC)") (class "Default")
      (node (ref "D20") (pin "C") (pinfunction "C_C") (pintype "passive"))
      (node (ref "SW54") (pin "1") (pinfunction "1_1") (pintype "passive"))
    )
    (net (code "51") (name "Net-(D21-PadC)") (class "Default")
      (node (ref "D21") (pin "C") (pinfunction "C_C") (pintype "passive"))
      (node (ref "SW5") (pin "1") (pinfunction "1_1") (pintype "passive"))
    )
    (net (code "52") (name "Net-(D22-PadC)") (class "Default")
      (node (ref "D22") (pin "C") (pinfunction "C_C") (pintype "passive"))
      (node (ref "SW6") (pin "1") (pinfunction "1_1") (pintype "passive"))
    )
    (net (code "53") (name "Net-(D23-PadC)") (class "Default")
      (node (ref "D23") (pin "C") (pinfunction "C_C") (pintype "passive"))
      (node (ref "SW7") (pin "1") (pinfunction "1_1") (pintype "passive"))
    )
    (net (code "54") (name "Net-(D24-PadC)") (class "Default")
      (node (ref "D24") (pin "C") (pinfunction "C_C") (pintype "passive"))
      (node (ref "SW8") (pin "1") (pinfunction "1_1") (pintype "passive"))
    )
    (net (code "55") (name "Net-(D25-PadC)") (class "Default")
      (node (ref "D25") (pin "C") (pinfunction "C_C") (pintype "passive"))
      (node (ref "SW9") (pin "1") (pinfunction "1_1") (pintype "passive"))
    )
    (net (code "56") (name "Net-(D26-PadC)") (class "Default")
      (node (ref "D26") (pin "C") (pinfunction "C_C") (pintype "passive"))
      (node (ref "SW11") (pin "1") (pinfunction "1_1") (pintype "passive"))
    )
    (net (code "57") (name "Net-(D27-PadC)") (class "Default")
      (node (ref "D27") (pin "C") (pinfunction "C_C") (pintype "passive"))
      (node (ref "SW12") (pin "1") (pinfunction "1_1") (pintype "passive"))
    )
    (net (code "58") (name "Net-(D28-PadC)") (class "Default")
      (node (ref "D28") (pin "C") (pinfunction "C_C") (pintype "passive"))
      (node (ref "SW18") (pin "1") (pinfunction "1_1") (pintype "passive"))
    )
    (net (code "59") (name "Net-(D29-PadC)") (class "Default")
      (node (ref "D29") (pin "C") (pinfunction "C_C") (pintype "passive"))
      (node (ref "SW17") (pin "1") (pinfunction "1_1") (pintype "passive"))
    )
    (net (code "60") (name "Net-(D30-PadC)") (class "Default")
      (node (ref "D30") (pin "C") (pinfunction "C_C") (pintype "passive"))
      (node (ref "SW13") (pin "1") (pinfunction "1_1") (pintype "passive"))
    )
    (net (code "61") (name "Net-(D31-PadC)") (class "Default")
      (node (ref "D31") (pin "C") (pinfunction "C_C") (pintype "passive"))
      (node (ref "SW14") (pin "1") (pinfunction "1_1") (pintype "passive"))
    )
    (net (code "62") (name "Net-(D32-PadC)") (class "Default")
      (node (ref "D32") (pin "C") (pinfunction "C_C") (pintype "passive"))
      (node (ref "SW16") (pin "1") (pinfunction "1_1") (pintype "passive"))
    )
    (net (code "63") (name "Net-(D33-PadC)") (class "Default")
      (node (ref "D33") (pin "C") (pinfunction "C_C") (pintype "passive"))
      (node (ref "SW15") (pin "1") (pinfunction "1_1") (pintype "passive"))
    )
    (net (code "64") (name "Net-(D34-PadC)") (class "Default")
      (node (ref "D34") (pin "C") (pinfunction "C_C") (pintype "passive"))
      (node (ref "SW10") (pin "1") (pinfunction "1_1") (pintype "passive"))
    )
    (net (code "65") (name "Net-(D35-PadC)") (class "Default")
      (node (ref "D35") (pin "C") (pinfunction "C_C") (pintype "passive"))
      (node (ref "SW19") (pin "1") (pinfunction "1_1") (pintype "passive"))
    )
    (net (code "66") (name "Net-(D36-PadC)") (class "Default")
      (node (ref "D36") (pin "C") (pinfunction "C_C") (pintype "passive"))
      (node (ref "SW20") (pin "1") (pinfunction "1_1") (pintype "passive"))
    )
    (net (code "67") (name "Net-(D37-PadC)") (class "Default")
      (node (ref "D37") (pin "C") (pinfunction "C_C") (pintype "passive"))
      (node (ref "SW23") (pin "1") (pinfunction "1_1") (pintype "passive"))
    )
    (net (code "68") (name "Net-(D38-PadC)") (class "Default")
      (node (ref "D38") (pin "C") (pinfunction "C_C") (pintype "passive"))
      (node (ref "SW24") (pin "1") (pinfunction "1_1") (pintype "passive"))
    )
    (net (code "69") (name "Net-(D39-PadC)") (class "Default")
      (node (ref "D39") (pin "C") (pinfunction "C_C") (pintype "passive"))
      (node (ref "SW25") (pin "1") (pinfunction "1_1") (pintype "passive"))
    )
    (net (code "70") (name "Net-(D40-PadC)") (class "Default")
      (node (ref "D40") (pin "C") (pinfunction "C_C") (pintype "passive"))
      (node (ref "SW27") (pin "1") (pinfunction "1_1") (pintype "passive"))
    )
    (net (code "71") (name "Net-(D41-PadC)") (class "Default")
      (node (ref "D41") (pin "C") (pinfunction "C_C") (pintype "passive"))
      (node (ref "SW28") (pin "1") (pinfunction "1_1") (pintype "passive"))
    )
    (net (code "72") (name "Net-(D42-PadC)") (class "Default")
      (node (ref "D42") (pin "C") (pinfunction "C_C") (pintype "passive"))
      (node (ref "SW34") (pin "1") (pinfunction "1_1") (pintype "passive"))
    )
    (net (code "73") (name "Net-(D43-PadC)") (class "Default")
      (node (ref "D43") (pin "C") (pinfunction "C_C") (pintype "passive"))
      (node (ref "SW33") (pin "1") (pinfunction "1_1") (pintype "passive"))
    )
    (net (code "74") (name "Net-(D44-PadC)") (class "Default")
      (node (ref "D44") (pin "C") (pinfunction "C_C") (pintype "passive"))
      (node (ref "SW29") (pin "1") (pinfunction "1_1") (pintype "passive"))
    )
    (net (code "75") (name "Net-(D45-PadC)") (class "Default")
      (node (ref "D45") (pin "C") (pinfunction "C_C") (pintype "passive"))
      (node (ref "SW30") (pin "1") (pinfunction "1_1") (pintype "passive"))
    )
    (net (code "76") (name "Net-(D46-PadC)") (class "Default")
      (node (ref "D46") (pin "C") (pinfunction "C_C") (pintype "passive"))
      (node (ref "SW32") (pin "1") (pinfunction "1_1") (pintype "passive"))
    )
    (net (code "77") (name "Net-(D47-PadC)") (class "Default")
      (node (ref "D47") (pin "C") (pinfunction "C_C") (pintype "passive"))
      (node (ref "SW31") (pin "1") (pinfunction "1_1") (pintype "passive"))
    )
    (net (code "78") (name "Net-(D48-PadC)") (class "Default")
      (node (ref "D48") (pin "C") (pinfunction "C_C") (pintype "passive"))
      (node (ref "SW26") (pin "1") (pinfunction "1_1") (pintype "passive"))
    )
    (net (code "79") (name "Net-(D49-PadC)") (class "Default")
      (node (ref "D49") (pin "C") (pinfunction "C_C") (pintype "passive"))
      (node (ref "SW35") (pin "1") (pinfunction "1_1") (pintype "passive"))
    )
    (net (code "80") (name "Net-(D50-PadC)") (class "Default")
      (node (ref "D50") (pin "C") (pinfunction "C_C") (pintype "passive"))
      (node (ref "SW36") (pin "1") (pinfunction "1_1") (pintype "passive"))
    )
    (net (code "81") (name "Net-(D51-PadC)") (class "Default")
      (node (ref "D51") (pin "C") (pinfunction "C_C") (pintype "passive"))
      (node (ref "SW21") (pin "1") (pinfunction "1_1") (pintype "passive"))
    )
    (net (code "82") (name "Net-(D52-PadC)") (class "Default")
      (node (ref "D52") (pin "C") (pinfunction "C_C") (pintype "passive"))
      (node (ref "SW22") (pin "1") (pinfunction "1_1") (pintype "passive"))
    )
    (net (code "83") (name "Net-(D53-PadC)") (class "Default")
      (node (ref "D53") (pin "C") (pinfunction "C_C") (pintype "passive"))
      (node (ref "SW37") (pin "1") (pinfunction "1_1") (pintype "passive"))
    )
    (net (code "84") (name "Net-(D54-PadC)") (class "Default")
      (node (ref "D54") (pin "C") (pinfunction "C_C") (pintype "passive"))
      (node (ref "SW38") (pin "1") (pinfunction "1_1") (pintype "passive"))
    )
    (net (code "85") (name "Net-(D55-PadC)") (class "Default")
      (node (ref "D55") (pin "C") (pinfunction "C_C") (pintype "passive"))
      (node (ref "SW41") (pin "1") (pinfunction "1_1") (pintype "passive"))
    )
    (net (code "86") (name "Net-(D56-PadC)") (class "Default")
      (node (ref "D56") (pin "C") (pinfunction "C_C") (pintype "passive"))
      (node (ref "SW42") (pin "1") (pinfunction "1_1") (pintype "passive"))
    )
    (net (code "87") (name "Net-(D57-PadC)") (class "Default")
      (node (ref "D57") (pin "C") (pinfunction "C_C") (pintype "passive"))
      (node (ref "SW43") (pin "1") (pinfunction "1_1") (pintype "passive"))
    )
    (net (code "88") (name "Net-(D58-PadC)") (class "Default")
      (node (ref "D58") (pin "C") (pinfunction "C_C") (pintype "passive"))
      (node (ref "SW45") (pin "1") (pinfunction "1_1") (pintype "passive"))
    )
    (net (code "89") (name "Net-(D59-PadC)") (class "Default")
      (node (ref "D59") (pin "C") (pinfunction "C_C") (pintype "passive"))
      (node (ref "SW50") (pin "1") (pinfunction "1_1") (pintype "passive"))
    )
    (net (code "90") (name "Net-(D60-PadC)") (class "Default")
      (node (ref "D60") (pin "C") (pinfunction "C_C") (pintype "passive"))
      (node (ref "SW65") (pin "1") (pinfunction "1_1") (pintype "passive"))
    )
    (net (code "91") (name "Net-(D61-PadC)") (class "Default")
      (node (ref "D61") (pin "C") (pinfunction "C_C") (pintype "passive"))
      (node (ref "SW64") (pin "1") (pinfunction "1_1") (pintype "passive"))
    )
    (net (code "92") (name "Net-(D62-PadC)") (class "Default")
      (node (ref "D62") (pin "C") (pinfunction "C_C") (pintype "passive"))
      (node (ref "SW57") (pin "1") (pinfunction "1_1") (pintype "passive"))
    )
    (net (code "93") (name "Net-(D63-PadC)") (class "Default")
      (node (ref "D63") (pin "C") (pinfunction "C_C") (pintype "passive"))
      (node (ref "SW61") (pin "1") (pinfunction "1_1") (pintype "passive"))
    )
    (net (code "94") (name "Net-(D64-PadC)") (class "Default")
      (node (ref "D64") (pin "C") (pinfunction "C_C") (pintype "passive"))
      (node (ref "SW63") (pin "1") (pinfunction "1_1") (pintype "passive"))
    )
    (net (code "95") (name "Net-(D65-PadC)") (class "Default")
      (node (ref "D65") (pin "C") (pinfunction "C_C") (pintype "passive"))
      (node (ref "SW62") (pin "1") (pinfunction "1_1") (pintype "passive"))
    )
    (net (code "96") (name "Net-(D66-PadC)") (class "Default")
      (node (ref "D66") (pin "C") (pinfunction "C_C") (pintype "passive"))
      (node (ref "SW44") (pin "1") (pinfunction "1_1") (pintype "passive"))
    )
    (net (code "97") (name "Net-(D67-PadC)") (class "Default")
      (node (ref "D67") (pin "C") (pinfunction "C_C") (pintype "passive"))
      (node (ref "SW66") (pin "1") (pinfunction "1_1") (pintype "passive"))
    )
    (net (code "98") (name "Net-(D68-PadC)") (class "Default")
      (node (ref "D68") (pin "C") (pinfunction "C_C") (pintype "passive"))
      (node (ref "SW67") (pin "1") (pinfunction "1_1") (pintype "passive"))
    )
    (net (code "99") (name "Net-(D69-PadC)") (class "Default")
      (node (ref "D69") (pin "C") (pinfunction "C_C") (pintype "passive"))
      (node (ref "SW39") (pin "1") (pinfunction "1_1") (pintype "passive"))
    )
    (net (code "100") (name "Net-(D70-PadC)") (class "Default")
      (node (ref "D70") (pin "C") (pinfunction "C_C") (pintype "passive"))
      (node (ref "SW40") (pin "1") (pinfunction "1_1") (pintype "passive"))
    )
    (net (code "101") (name "Net-(D71-PadC)") (class "Default")
      (node (ref "D71") (pin "C") (pinfunction "C_C") (pintype "passive"))
      (node (ref "SW68") (pin "1") (pinfunction "1_1") (pintype "passive"))
    )
    (net (code "102") (name "Net-(D72-PadC)") (class "Default")
      (node (ref "D72") (pin "C") (pinfunction "C_C") (pintype "passive"))
      (node (ref "SW69") (pin "1") (pinfunction "1_1") (pintype "passive"))
    )
    (net (code "103") (name "Net-(D73-PadC)") (class "Default")
      (node (ref "D73") (pin "C") (pinfunction "C_C") (pintype "passive"))
      (node (ref "SW70") (pin "1") (pinfunction "1_1") (pintype "passive"))
    )
    (net (code "104") (name "Net-(D74-PadC)") (class "Default")
      (node (ref "D74") (pin "C") (pinfunction "C_C") (pintype "passive"))
      (node (ref "SW71") (pin "1") (pinfunction "1_1") (pintype "passive"))
    )
    (net (code "105") (name "Net-(D75-PadC)") (class "Default")
      (node (ref "D75") (pin "C") (pinfunction "C_C") (pintype "passive"))
      (node (ref "SW72") (pin "1") (pinfunction "1_1") (pintype "passive"))
    )
    (net (code "106") (name "Net-(D76-PadC)") (class "Default")
      (node (ref "D76") (pin "C") (pinfunction "C_C") (pintype "passive"))
      (node (ref "SW73") (pin "1") (pinfunction "1_1") (pintype "passive"))
    )
    (net (code "107") (name "Net-(D77-PadC)") (class "Default")
      (node (ref "D77") (pin "C") (pinfunction "C_C") (pintype "passive"))
      (node (ref "SW74") (pin "1") (pinfunction "1_1") (pintype "passive"))
    )
    (net (code "108") (name "Net-(D78-PadC)") (class "Default")
      (node (ref "D78") (pin "C") (pinfunction "C_C") (pintype "passive"))
      (node (ref "SW75") (pin "1") (pinfunction "1_1") (pintype "passive"))
    )
    (net (code "109") (name "Net-(D79-PadC)") (class "Default")
      (node (ref "D79") (pin "C") (pinfunction "C_C") (pintype "passive"))
      (node (ref "SW76") (pin "1") (pinfunction "1_1") (pintype "passive"))
    )
    (net (code "110") (name "Net-(D80-PadC)") (class "Default")
      (node (ref "D80") (pin "C") (pinfunction "C_C") (pintype "passive"))
      (node (ref "SW78") (pin "1") (pinfunction "1_1") (pintype "passive"))
    )
    (net (code "111") (name "Net-(D81-PadC)") (class "Default")
      (node (ref "D81") (pin "C") (pinfunction "C_C") (pintype "passive"))
      (node (ref "SW77") (pin "1") (pinfunction "1_1") (pintype "passive"))
    )
    (net (code "112") (name "Net-(D82-PadC)") (class "Default")
      (node (ref "D82") (pin "C") (pinfunction "C_C") (pintype "passive"))
      (node (ref "SW79") (pin "1") (pinfunction "1_1") (pintype "passive"))
    )
    (net (code "113") (name "Net-(D83-PadC)") (class "Default")
      (node (ref "D83") (pin "C") (pinfunction "C_C") (pintype "passive"))
      (node (ref "SW81") (pin "1") (pinfunction "1_1") (pintype "passive"))
    )
    (net (code "114") (name "Net-(D84-PadC)") (class "Default")
      (node (ref "D84") (pin "C") (pinfunction "C_C") (pintype "passive"))
      (node (ref "SW80") (pin "1") (pinfunction "1_1") (pintype "passive"))
    )
    (net (code "115") (name "Net-(D85-PadC)") (class "Default")
      (node (ref "D85") (pin "C") (pinfunction "C_C") (pintype "passive"))
      (node (ref "SW82") (pin "1") (pinfunction "1_1") (pintype "passive"))
    )
    (net (code "116") (name "Net-(D89-PadC)") (class "Default")
      (node (ref "D89") (pin "C") (pinfunction "C_C") (pintype "passive"))
      (node (ref "SW87") (pin "1") (pinfunction "1_1") (pintype "passive"))
    )
    (net (code "117") (name "Net-(D91-PadC)") (class "Default")
      (node (ref "D91") (pin "C") (pinfunction "C_C") (pintype "passive"))
      (node (ref "SW93") (pin "1") (pinfunction "1_1") (pintype "passive"))
    )
    (net (code "118") (name "Net-(D94-PadC)") (class "Default")
      (node (ref "D94") (pin "C") (pinfunction "C_C") (pintype "passive"))
      (node (ref "SW97") (pin "1") (pinfunction "1_1") (pintype "passive"))
    )
    (net (code "119") (name "Net-(D98-PadC)") (class "Default")
      (node (ref "D98") (pin "C") (pinfunction "C_C") (pintype "passive"))
      (node (ref "SW99") (pin "1") (pinfunction "1_1") (pintype "passive"))
    )
    (net (code "120") (name "Net-(D103-PadC)") (class "Default")
      (node (ref "D103") (pin "C") (pinfunction "C_C") (pintype "passive"))
      (node (ref "SW105") (pin "1") (pinfunction "1_1") (pintype "passive"))
    )
    (net (code "121") (name "Net-(LED1-DI)") (class "Default")
      (node (ref "LED1") (pin "4") (pinfunction "DI_4") (pintype "input"))
      (node (ref "LED28") (pin "2") (pinfunction "DO_2") (pintype "output"))
    )
    (net (code "122") (name "Net-(LED1-DO)") (class "Default")
      (node (ref "LED1") (pin "2") (pinfunction "DO_2") (pintype "output"))
      (node (ref "LED2") (pin "4") (pinfunction "DI_4") (pintype "input"))
    )
    (net (code "123") (name "Net-(LED2-DO)") (class "Default")
      (node (ref "LED2") (pin "2") (pinfunction "DO_2") (pintype "output"))
      (node (ref "LED3") (pin "4") (pinfunction "DI_4") (pintype "input"))
    )
    (net (code "124") (name "Net-(LED3-DO)") (class "Default")
      (node (ref "LED3") (pin "2") (pinfunction "DO_2") (pintype "output"))
      (node (ref "LED4") (pin "4") (pinfunction "DI_4") (pintype "input"))
    )
    (net (code "125") (name "Net-(LED4-DO)") (class "Default")
      (node (ref "LED4") (pin "2") (pinfunction "DO_2") (pintype "output"))
      (node (ref "LED5") (pin "4") (pinfunction "DI_4") (pintype "input"))
    )
    (net (code "126") (name "Net-(LED5-DO)") (class "Default")
      (node (ref "LED5") (pin "2") (pinfunction "DO_2") (pintype "output"))
      (node (ref "LED6") (pin "4") (pinfunction "DI_4") (pintype "input"))
    )
    (net (code "127") (name "Net-(LED6-DO)") (class "Default")
      (node (ref "LED6") (pin "2") (pinfunction "DO_2") (pintype "output"))
      (node (ref "LED7") (pin "4") (pinfunction "DI_4") (pintype "input"))
    )
    (net (code "128") (name "Net-(LED7-DO)") (class "Default")
      (node (ref "LED7") (pin "2") (pinfunction "DO_2") (pintype "output"))
      (node (ref "LED8") (pin "4") (pinfunction "DI_4") (pintype "input"))
    )
    (net (code "129") (name "Net-(LED8-DO)") (class "Default")
      (node (ref "LED8") (pin "2") (pinfunction "DO_2") (pintype "output"))
      (node (ref "LED9") (pin "4") (pinfunction "DI_4") (pintype "input"))
    )
    (net (code "130") (name "Net-(LED10-DI)") (class "Default")
      (node (ref "LED10") (pin "4") (pinfunction "DI_4") (pintype "input"))
      (node (ref "LED9") (pin "2") (pinfunction "DO_2") (pintype "output"))
    )
    (net (code "131") (name "Net-(LED10-DO)") (class "Default")
      (node (ref "LED10") (pin "2") (pinfunction "DO_2") (pintype "output"))
      (node (ref "LED11") (pin "4") (pinfunction "DI_4") (pintype "input"))
    )
    (net (code "132") (name "Net-(LED11-DO)") (class "Default")
      (node (ref "LED11") (pin "2") (pinfunction "DO_2") (pintype "output"))
      (node (ref "LED12") (pin "4") (pinfunction "DI_4") (pintype "input"))
    )
    (net (code "133") (name "Net-(LED12-DO)") (class "Default")
      (node (ref "LED12") (pin "2") (pinfunction "DO_2") (pintype "output"))
      (node (ref "LED29") (pin "4") (pinfunction "DI_4") (pintype "input"))
    )
    (net (code "134") (name "Net-(LED13-DI)") (class "Default")
      (node (ref "LED13") (pin "4") (pinfunction "DI_4") (pintype "input"))
      (node (ref "LED99") (pin "2") (pinfunction "DO_2") (pintype "output"))
    )
    (net (code "135") (name "Net-(LED13-DO)") (class "Default")
      (node (ref "LED13") (pin "2") (pinfunction "DO_2") (pintype "output"))
      (node (ref "LED14") (pin "4") (pinfunction "DI_4") (pintype "input"))
    )
    (net (code "136") (name "Net-(LED14-DO)") (class "Default")
      (node (ref "LED14") (pin "2") (pinfunction "DO_2") (pintype "output"))
      (node (ref "LED15") (pin "4") (pinfunction "DI_4") (pintype "input"))
    )
    (net (code "137") (name "Net-(LED15-DO)") (class "Default")
      (node (ref "LED15") (pin "2") (pinfunction "DO_2") (pintype "output"))
      (node (ref "LED16") (pin "4") (pinfunction "DI_4") (pintype "input"))
    )
    (net (code "138") (name "Net-(LED16-DO)") (class "Default")
      (node (ref "LED16") (pin "2") (pinfunction "DO_2") (pintype "output"))
      (node (ref "LED17") (pin "4") (pinfunction "DI_4") (pintype "input"))
    )
    (net (code "139") (name "Net-(LED17-DO)") (class "Default")
      (node (ref "LED17") (pin "2") (pinfunction "DO_2") (pintype "output"))
      (node (ref "LED18") (pin "4") (pinfunction "DI_4") (pintype "input"))
    )
    (net (code "140") (name "Net-(LED18-DO)") (class "Default")
      (node (ref "LED18") (pin "2") (pinfunction "DO_2") (pintype "output"))
      (node (ref "LED19") (pin "4") (pinfunction "DI_4") (pintype "input"))
    )
    (net (code "141") (name "Net-(LED19-DO)") (class "Default")
      (node (ref "LED19") (pin "2") (pinfunction "DO_2") (pintype "output"))
      (node (ref "LED20") (pin "4") (pinfunction "DI_4") (pintype "input"))
    )
    (net (code "142") (name "Net-(LED20-DO)") (class "Default")
      (node (ref "LED20") (pin "2") (pinfunction "DO_2") (pintype "output"))
      (node (ref "LED21") (pin "4") (pinfunction "DI_4") (pintype "input"))
    )
    (net (code "143") (name "Net-(LED21-DO)") (class "Default")
      (node (ref "LED21") (pin "2") (pinfunction "DO_2") (pintype "output"))
      (node (ref "LED22") (pin "4") (pinfunction "DI_4") (pintype "input"))
    )
    (net (code "144") (name "Net-(LED22-DO)") (class "Default")
      (node (ref "LED22") (pin "2") (pinfunction "DO_2") (pintype "output"))
      (node (ref "LED23") (pin "4") (pinfunction "DI_4") (pintype "input"))
    )
    (net (code "145") (name "Net-(LED23-DO)") (class "Default")
      (node (ref "LED23") (pin "2") (pinfunction "DO_2") (pintype "output"))
      (node (ref "LED24") (pin "4") (pinfunction "DI_4") (pintype "input"))
    )
    (net (code "146") (name "Net-(LED24-DO)") (class "Default")
      (node (ref "LED24") (pin "2") (pinfunction "DO_2") (pintype "output"))
      (node (ref "LED25") (pin "4") (pinfunction "DI_4") (pintype "input"))
    )
    (net (code "147") (name "Net-(LED25-DO)") (class "Default")
      (node (ref "LED25") (pin "2") (pinfunction "DO_2") (pintype "output"))
      (node (ref "LED26") (pin "4") (pinfunction "DI_4") (pintype "input"))
    )
    (net (code "148") (name "Net-(LED26-DO)") (class "Default")
      (node (ref "LED26") (pin "2") (pinfunction "DO_2") (pintype "output"))
      (node (ref "LED27") (pin "4") (pinfunction "DI_4") (pintype "input"))
    )
    (net (code "149") (name "Net-(LED27-DO)") (class "Default")
      (node (ref "LED27") (pin "2") (pinfunction "DO_2") (pintype "output"))
      (node (ref "LED28") (pin "4") (pinfunction "DI_4") (pintype "input"))
    )
    (net (code "150") (name "Net-(LED29-DO)") (class "Default")
      (node (ref "LED29") (pin "2") (pinfunction "DO_2") (pintype "output"))
      (node (ref "LED30") (pin "4") (pinfunction "DI_4") (pintype "input"))
    )
    (net (code "151") (name "Net-(LED30-DO)") (class "Default")
      (node (ref "LED30") (pin "2") (pinfunction "DO_2") (pintype "output"))
      (node (ref "LED31") (pin "4") (pinfunction "DI_4") (pintype "input"))
    )
    (net (code "152") (name "Net-(LED31-DO)") (class "Default")
      (node (ref "LED31") (pin "2") (pinfunction "DO_2") (pintype "output"))
      (node (ref "LED32") (pin "4") (pinfunction "DI_4") (pintype "input"))
    )
    (net (code "153") (name "Net-(LED32-DO)") (class "Default")
      (node (ref "LED32") (pin "2") (pinfunction "DO_2") (pintype "output"))
      (node (ref "LED33") (pin "4") (pinfunction "DI_4") (pintype "input"))
    )
    (net (code "154") (name "Net-(LED33-DO)") (class "Default")
      (node (ref "LED33") (pin "2") (pinfunction "DO_2") (pintype "output"))
      (node (ref "LED34") (pin "4") (pinfunction "DI_4") (pintype "input"))
    )
    (net (code "155") (name "Net-(LED34-DO)") (class "Default")
      (node (ref "LED34") (pin "2") (pinfunction "DO_2") (pintype "output"))
      (node (ref "LED35") (pin "4") (pinfunction "DI_4") (pintype "input"))
    )
    (net (code "156") (name "Net-(LED35-DO)") (class "Default")
      (node (ref "LED35") (pin "2") (pinfunction "DO_2") (pintype "output"))
      (node (ref "LED36") (pin "4") (pinfunction "DI_4") (pintype "input"))
    )
    (net (code "157") (name "Net-(LED36-DO)") (class "Default")
      (node (ref "LED36") (pin "2") (pinfunction "DO_2") (pintype "output"))
      (node (ref "LED37") (pin "4") (pinfunction "DI_4") (pintype "input"))
    )
    (net (code "158") (name "Net-(LED37-DO)") (class "Default")
      (node (ref "LED37") (pin "2") (pinfunction "DO_2") (pintype "output"))
      (node (ref "LED38") (pin "4") (pinfunction "DI_4") (pintype "input"))
    )
    (net (code "159") (name "Net-(LED38-DO)") (class "Default")
      (node (ref "LED38") (pin "2") (pinfunction "DO_2") (pintype "output"))
      (node (ref "LED39") (pin "4") (pinfunction "DI_4") (pintype "input"))
    )
    (net (code "160") (name "Net-(LED39-DO)") (class "Default")
      (node (ref "LED39") (pin "2") (pinfunction "DO_2") (pintype "output"))
      (node (ref "LED40") (pin "4") (pinfunction "DI_4") (pintype "input"))
    )
    (net (code "161") (name "Net-(LED40-DO)") (class "Default")
      (node (ref "LED40") (pin "2") (pinfunction "DO_2") (pintype "output"))
      (node (ref "LED41") (pin "4") (pinfunction "DI_4") (pintype "input"))
    )
    (net (code "162") (name "Net-(LED41-DO)") (class "Default")
      (node (ref "LED41") (pin "2") (pinfunction "DO_2") (pintype "output"))
      (node (ref "LED42") (pin "4") (pinfunction "DI_4") (pintype "input"))
    )
    (net (code "163") (name "Net-(LED42-DO)") (class "Default")
      (node (ref "LED42") (pin "2") (pinfunction "DO_2") (pintype "output"))
      (node (ref "LED43") (pin "4") (pinfunction "DI_4") (pintype "input"))
    )
    (net (code "164") (name "Net-(LED43-DO)") (class "Default")
      (node (ref "LED43") (pin "2") (pinfunction "DO_2") (pintype "output"))
      (node (ref "LED44") (pin "4") (pinfunction "DI_4") (pintype "input"))
    )
    (net (code "165") (name "Net-(LED44-DO)") (class "Default")
      (node (ref "LED44") (pin "2") (pinfunction "DO_2") (pintype "output"))
      (node (ref "LED45") (pin "4") (pinfunction "DI_4") (pintype "input"))
    )
    (net (code "166") (name "Net-(LED45-DO)") (class "Default")
      (node (ref "LED45") (pin "2") (pinfunction "DO_2") (pintype "output"))
      (node (ref "LED46") (pin "4") (pinfunction "DI_4") (pintype "input"))
    )
    (net (code "167") (name "Net-(LED46-DO)") (class "Default")
      (node (ref "LED46") (pin "2") (pinfunction "DO_2") (pintype "output"))
      (node (ref "LED47") (pin "4") (pinfunction "DI_4") (pintype "input"))
    )
    (net (code "168") (name "Net-(LED47-DO)") (class "Default")
      (node (ref "LED47") (pin "2") (pinfunction "DO_2") (pintype "output"))
      (node (ref "LED48") (pin "4") (pinfunction "DI_4") (pintype "input"))
    )
    (net (code "169") (name "Net-(LED48-DO)") (class "Default")
      (node (ref "LED48") (pin "2") (pinfunction "DO_2") (pintype "output"))
      (node (ref "LED49") (pin "4") (pinfunction "DI_4") (pintype "input"))
    )
    (net (code "170") (name "Net-(LED49-DO)") (class "Default")
      (node (ref "LED49") (pin "2") (pinfunction "DO_2") (pintype "output"))
      (node (ref "LED50") (pin "4") (pinfunction "DI_4") (pintype "input"))
    )
    (net (code "171") (name "Net-(LED50-DO)") (class "Default")
      (node (ref "LED50") (pin "2") (pinfunction "DO_2") (pintype "output"))
      (node (ref "LED51") (pin "4") (pinfunction "DI_4") (pintype "input"))
    )
    (net (code "172") (name "Net-(LED51-DO)") (class "Default")
      (node (ref "LED51") (pin "2") (pinfunction "DO_2") (pintype "output"))
      (node (ref "LED52") (pin "4") (pinfunction "DI_4") (pintype "input"))
    )
    (net (code "173") (name "Net-(LED52-DO)") (class "Default")
      (node (ref "LED52") (pin "2") (pinfunction "DO_2") (pintype "output"))
      (node (ref "LED53") (pin "4") (pinfunction "DI_4") (pintype "input"))
    )
    (net (code "174") (name "Net-(LED53-DO)") (class "Default")
      (node (ref "LED53") (pin "2") (pinfunction "DO_2") (pintype "output"))
      (node (ref "LED54") (pin "4") (pinfunction "DI_4") (pintype "input"))
    )
    (net (code "175") (name "Net-(LED54-DO)") (class "Default")
      (node (ref "LED54") (pin "2") (pinfunction "DO_2") (pintype "output"))
      (node (ref "LED55") (pin "4") (pinfunction "DI_4") (pintype "input"))
    )
    (net (code "176") (name "Net-(LED55-DO)") (class "Default")
      (node (ref "LED55") (pin "2") (pinfunction "DO_2") (pintype "output"))
      (node (ref "LED56") (pin "4") (pinfunction "DI_4") (pintype "input"))
    )
    (net (code "177") (name "Net-(LED56-DO)") (class "Default")
      (node (ref "LED56") (pin "2") (pinfunction "DO_2") (pintype "output"))
      (node (ref "LED57") (pin "4") (pinfunction "DI_4") (pintype "input"))
    )
    (net (code "178") (name "Net-(LED57-DO)") (class "Default")
      (node (ref "LED57") (pin "2") (pinfunction "DO_2") (pintype "output"))
      (node (ref "LED58") (pin "4") (pinfunction "DI_4") (pintype "input"))
    )
    (net (code "179") (name "Net-(LED58-DO)") (class "Default")
      (node (ref "LED58") (pin "2") (pinfunction "DO_2") (pintype "output"))
      (node (ref "LED59") (pin "4") (pinfunction "DI_4") (pintype "input"))
    )
    (net (code "180") (name "Net-(LED59-DO)") (class "Default")
      (node (ref "LED59") (pin "2") (pinfunction "DO_2") (pintype "output"))
      (node (ref "LED60") (pin "4") (pinfunction "DI_4") (pintype "input"))
    )
    (net (code "181") (name "Net-(LED60-DO)") (class "Default")
      (node (ref "LED60") (pin "2") (pinfunction "DO_2") (pintype "output"))
      (node (ref "LED61") (pin "4") (pinfunction "DI_4") (pintype "input"))
    )
    (net (code "182") (name "Net-(LED61-DO)") (class "Default")
      (node (ref "LED61") (pin "2") (pinfunction "DO_2") (pintype "output"))
      (node (ref "LED62") (pin "4") (pinfunction "DI_4") (pintype "input"))
    )
    (net (code "183") (name "Net-(LED62-DO)") (class "Default")
      (node (ref "LED62") (pin "2") (pinfunction "DO_2") (pintype "output"))
      (node (ref "LED63") (pin "4") (pinfunction "DI_4") (pintype "input"))
    )
    (net (code "184") (name "Net-(LED63-DO)") (class "Default")
      (node (ref "LED63") (pin "2") (pinfunction "DO_2") (pintype "output"))
      (node (ref "LED64") (pin "4") (pinfunction "DI_4") (pintype "input"))
    )
    (net (code "185") (name "Net-(LED64-DO)") (class "Default")
      (node (ref "LED64") (pin "2") (pinfunction "DO_2") (pintype "output"))
      (node (ref "LED65") (pin "4") (pinfunction "DI_4") (pintype "input"))
    )
    (net (code "186") (name "Net-(LED65-DO)") (class "Default")
      (node (ref "LED65") (pin "2") (pinfunction "DO_2") (pintype "output"))
      (node (ref "LED66") (pin "4") (pinfunction "DI_4") (pintype "input"))
    )
    (net (code "187") (name "Net-(LED66-DO)") (class "Default")
      (node (ref "LED66") (pin "2") (pinfunction "DO_2") (pintype "output"))
      (node (ref "LED67") (pin "4") (pinfunction "DI_4") (pintype "input"))
    )
    (net (code "188") (name "Net-(LED67-DO)") (class "Default")
      (node (ref "LED67") (pin "2") (pinfunction "DO_2") (pintype "output"))
      (node (ref "LED68") (pin "4") (pinfunction "DI_4") (pintype "input"))
    )
    (net (code "189") (name "Net-(LED68-DO)") (class "Default")
      (node (ref "LED68") (pin "2") (pinfunction "DO_2") (pintype "output"))
      (node (ref "LED69") (pin "4") (pinfunction "DI_4") (pintype "input"))
    )
    (net (code "190") (name "Net-(LED69-DO)") (class "Default")
      (node (ref "LED69") (pin "2") (pinfunction "DO_2") (pintype "output"))
      (node (ref "LED70") (pin "4") (pinfunction "DI_4") (pintype "input"))
    )
    (net (code "191") (name "Net-(LED70-DO)") (class "Default")
      (node (ref "LED70") (pin "2") (pinfunction "DO_2") (pintype "output"))
      (node (ref "LED71") (pin "4") (pinfunction "DI_4") (pintype "input"))
    )
    (net (code "192") (name "Net-(LED71-DO)") (class "Default")
      (node (ref "LED71") (pin "2") (pinfunction "DO_2") (pintype "output"))
      (node (ref "LED72") (pin "4") (pinfunction "DI_4") (pintype "input"))
    )
    (net (code "193") (name "Net-(LED72-DO)") (class "Default")
      (node (ref "LED72") (pin "2") (pinfunction "DO_2") (pintype "output"))
      (node (ref "LED73") (pin "4") (pinfunction "DI_4") (pintype "input"))
    )
    (net (code "194") (name "Net-(LED73-DO)") (class "Default")
      (node (ref "LED73") (pin "2") (pinfunction "DO_2") (pintype "output"))
      (node (ref "LED74") (pin "4") (pinfunction "DI_4") (pintype "input"))
    )
    (net (code "195") (name "Net-(LED74-DO)") (class "Default")
      (node (ref "LED74") (pin "2") (pinfunction "DO_2") (pintype "output"))
      (node (ref "LED75") (pin "4") (pinfunction "DI_4") (pintype "input"))
    )
    (net (code "196") (name "Net-(LED75-DO)") (class "Default")
      (node (ref "LED75") (pin "2") (pinfunction "DO_2") (pintype "output"))
      (node (ref "LED76") (pin "4") (pinfunction "DI_4") (pintype "input"))
    )
    (net (code "197") (name "Net-(LED76-DO)") (class "Default")
      (node (ref "LED76") (pin "2") (pinfunction "DO_2") (pintype "output"))
      (node (ref "LED77") (pin "4") (pinfunction "DI_4") (pintype "input"))
    )
    (net (code "198") (name "Net-(LED77-DO)") (class "Default")
      (node (ref "LED77") (pin "2") (pinfunction "DO_2") (pintype "output"))
      (node (ref "LED78") (pin "4") (pinfunction "DI_4") (pintype "input"))
    )
    (net (code "199") (name "Net-(LED78-DO)") (class "Default")
      (node (ref "LED78") (pin "2") (pinfunction "DO_2") (pintype "output"))
      (node (ref "LED79") (pin "4") (pinfunction "DI_4") (pintype "input"))
    )
    (net (code "200") (name "Net-(LED79-DO)") (class "Default")
      (node (ref "LED79") (pin "2") (pinfunction "DO_2") (pintype "output"))
      (node (ref "LED80") (pin "4") (pinfunction "DI_4") (pintype "input"))
    )
    (net (code "201") (name "Net-(LED80-DO)") (class "Default")
      (node (ref "LED80") (pin "2") (pinfunction "DO_2") (pintype "output"))
      (node (ref "LED81") (pin "4") (pinfunction "DI_4") (pintype "input"))
    )
    (net (code "202") (name "Net-(LED81-DO)") (class "Default")
      (node (ref "LED81") (pin "2") (pinfunction "DO_2") (pintype "output"))
      (node (ref "LED82") (pin "4") (pinfunction "DI_4") (pintype "input"))
    )
    (net (code "203") (name "Net-(LED82-DO)") (class "Default")
      (node (ref "LED82") (pin "2") (pinfunction "DO_2") (pintype "output"))
      (node (ref "LED83") (pin "4") (pinfunction "DI_4") (pintype "input"))
    )
    (net (code "204") (name "Net-(LED83-DO)") (class "Default")
      (node (ref "LED83") (pin "2") (pinfunction "DO_2") (pintype "output"))
      (node (ref "LED84") (pin "4") (pinfunction "DI_4") (pintype "input"))
    )
    (net (code "205") (name "Net-(LED84-DO)") (class "Default")
      (node (ref "LED84") (pin "2") (pinfunction "DO_2") (pintype "output"))
      (node (ref "LED85") (pin "4") (pinfunction "DI_4") (pintype "input"))
    )
    (net (code "206") (name "Net-(LED85-DO)") (class "Default")
      (node (ref "LED85") (pin "2") (pinfunction "DO_2") (pintype "output"))
      (node (ref "LED86") (pin "4") (pinfunction "DI_4") (pintype "input"))
    )
    (net (code "207") (name "Net-(LED86-DO)") (class "Default")
      (node (ref "LED86") (pin "2") (pinfunction "DO_2") (pintype "output"))
      (node (ref "LED87") (pin "4") (pinfunction "DI_4") (pintype "input"))
    )
    (net (code "208") (name "Net-(LED87-DO)") (class "Default")
      (node (ref "LED87") (pin "2") (pinfunction "DO_2") (pintype "output"))
      (node (ref "LED88") (pin "4") (pinfunction "DI_4") (pintype "input"))
    )
    (net (code "209") (name "Net-(LED88-DO)") (class "Default")
      (node (ref "LED88") (pin "2") (pinfunction "DO_2") (pintype "output"))
      (node (ref "LED89") (pin "4") (pinfunction "DI_4") (pintype "input"))
    )
    (net (code "210") (name "Net-(LED89-DO)") (class "Default")
      (node (ref "LED89") (pin "2") (pinfunction "DO_2") (pintype "output"))
      (node (ref "LED90") (pin "4") (pinfunction "DI_4") (pintype "input"))
    )
    (net (code "211") (name "Net-(LED91-DO)") (class "Default")
      (node (ref "LED91") (pin "2") (pinfunction "DO_2") (pintype "output"))
      (node (ref "LED92") (pin "4") (pinfunction "DI_4") (pintype "input"))
    )
    (net (code "212") (name "Net-(LED92-DO)") (class "Default")
      (node (ref "LED92") (pin "2") (pinfunction "DO_2") (pintype "output"))
      (node (ref "LED93") (pin "4") (pinfunction "DI_4") (pintype "input"))
    )
    (net (code "213") (name "Net-(LED93-DO)") (class "Default")
      (node (ref "LED93") (pin "2") (pinfunction "DO_2") (pintype "output"))
      (node (ref "LED94") (pin "4") (pinfunction "DI_4") (pintype "input"))
    )
    (net (code "214") (name "Net-(LED94-DO)") (class "Default")
      (node (ref "LED94") (pin "2") (pinfunction "DO_2") (pintype "output"))
      (node (ref "LED95") (pin "4") (pinfunction "DI_4") (pintype "input"))
    )
    (net (code "215") (name "Net-(LED95-DO)") (class "Default")
      (node (ref "LED95") (pin "2") (pinfunction "DO_2") (pintype "output"))
      (node (ref "LED96") (pin "4") (pinfunction "DI_4") (pintype "input"))
    )
    (net (code "216") (name "Net-(LED96-DO)") (class "Default")
      (node (ref "LED96") (pin "2") (pinfunction "DO_2") (pintype "output"))
      (node (ref "LED97") (pin "4") (pinfunction "DI_4") (pintype "input"))
    )
    (net (code "217") (name "Net-(LED97-DO)") (class "Default")
      (node (ref "LED97") (pin "2") (pinfunction "DO_2") (pintype "output"))
      (node (ref "LED98") (pin "4") (pinfunction "DI_4") (pintype "input"))
    )
    (net (code "218") (name "Net-(LED98-DO)") (class "Default")
      (node (ref "LED98") (pin "2") (pinfunction "DO_2") (pintype "output"))
      (node (ref "LED99") (pin "4") (pinfunction "DI_4") (pintype "input"))
    )
    (net (code "219") (name "Net-(U$60-XTAL1)") (class "Default")
      (node (ref "C15") (pin "1") (pinfunction "1_1") (pintype "bidirectional"))
      (node (ref "R10") (pin "1") (pinfunction "1_1") (pintype "bidirectional"))
      (node (ref "U$60") (pin "P$1") (pinfunction "XTAL1_P$1") (pintype "bidirectional"))
      (node (ref "U1") (pin "17") (pinfunction "XTAL1_17") (pintype "bidirectional"))
    )
    (net (code "220") (name "Net-(U$60-XTAL2)") (class "Default")
      (node (ref "C16") (pin "1") (pinfunction "1_1") (pintype "bidirectional"))
      (node (ref "R10") (pin "2") (pinfunction "2_2") (pintype "bidirectional"))
      (node (ref "U$60") (pin "P$3") (pinfunction "XTAL2_P$3") (pintype "bidirectional"))
      (node (ref "U1") (pin "16") (pinfunction "XTAL2_16") (pintype "bidirectional"))
    )
    (net (code "221") (name "Net-(U1-AREF)") (class "Default")
      (node (ref "C13") (pin "1") (pinfunction "1_1") (pintype "bidirectional"))
      (node (ref "U1") (pin "42") (pinfunction "AREF_42") (pintype "bidirectional"))
    )
    (net (code "222") (name "Net-(U1-D+)") (class "Default")
      (node (ref "R8") (pin "1") (pinfunction "1_1") (pintype "bidirectional"))
      (node (ref "U1") (pin "4") (pinfunction "D+_4") (pintype "bidirectional"))
    )
    (net (code "223") (name "Net-(U1-D-)") (class "Default")
      (node (ref "R7") (pin "1") (pinfunction "1_1") (pintype "bidirectional"))
      (node (ref "U1") (pin "3") (pinfunction "D-_3") (pintype "bidirectional"))
    )
    (net (code "224") (name "Net-(U1-UCAP)") (class "Default")
      (node (ref "C14") (pin "1") (pinfunction "1_1") (pintype "bidirectional"))
      (node (ref "U1") (pin "6") (pinfunction "UCAP_6") (pintype "bidirectional"))
    )
    (net (code "225") (name "unconnected-(J1-ID-Pad4)") (class "Default")
      (node (ref "J1") (pin "4") (pinfunction "ID_4") (pintype "bidirectional"))
    )
    (net (code "226") (name "unconnected-(LED90-DO-Pad2)") (class "Default")
      (node (ref "LED90") (pin "2") (pinfunction "DO_2") (pintype "output"))
    )
    (net (code "227") (name "unconnected-(U1-PE2(~{HWB})-Pad33)") (class "Default")
      (node (ref "U1") (pin "33") (pinfunction "PE2(~{HWB})_33") (pintype "bidirectional"))
    )
  )
)
